# Sheet1.net
KiCad netlist of a schematic drawn in Altium Designer
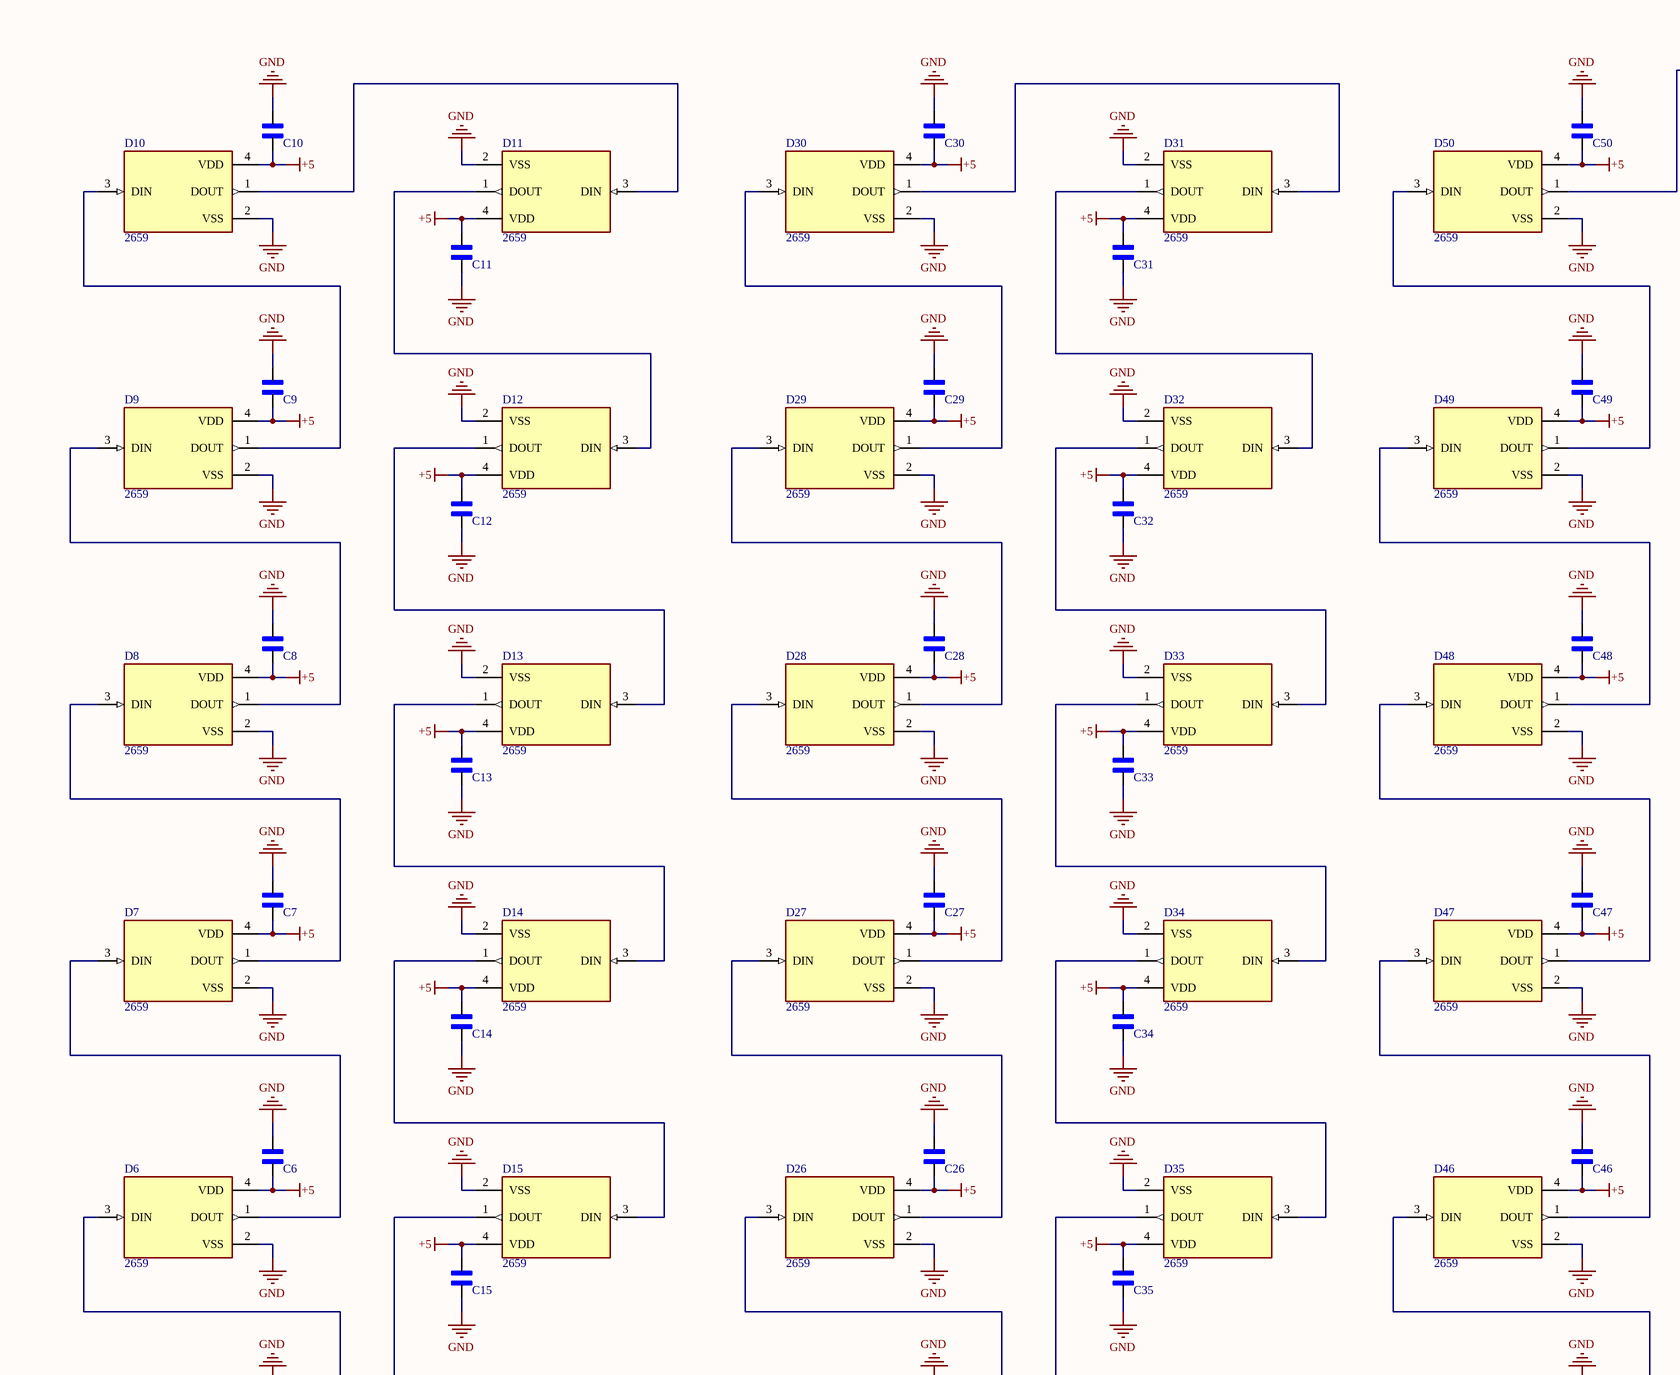
[diagram p0: Sheet1.SchDoc, top left]
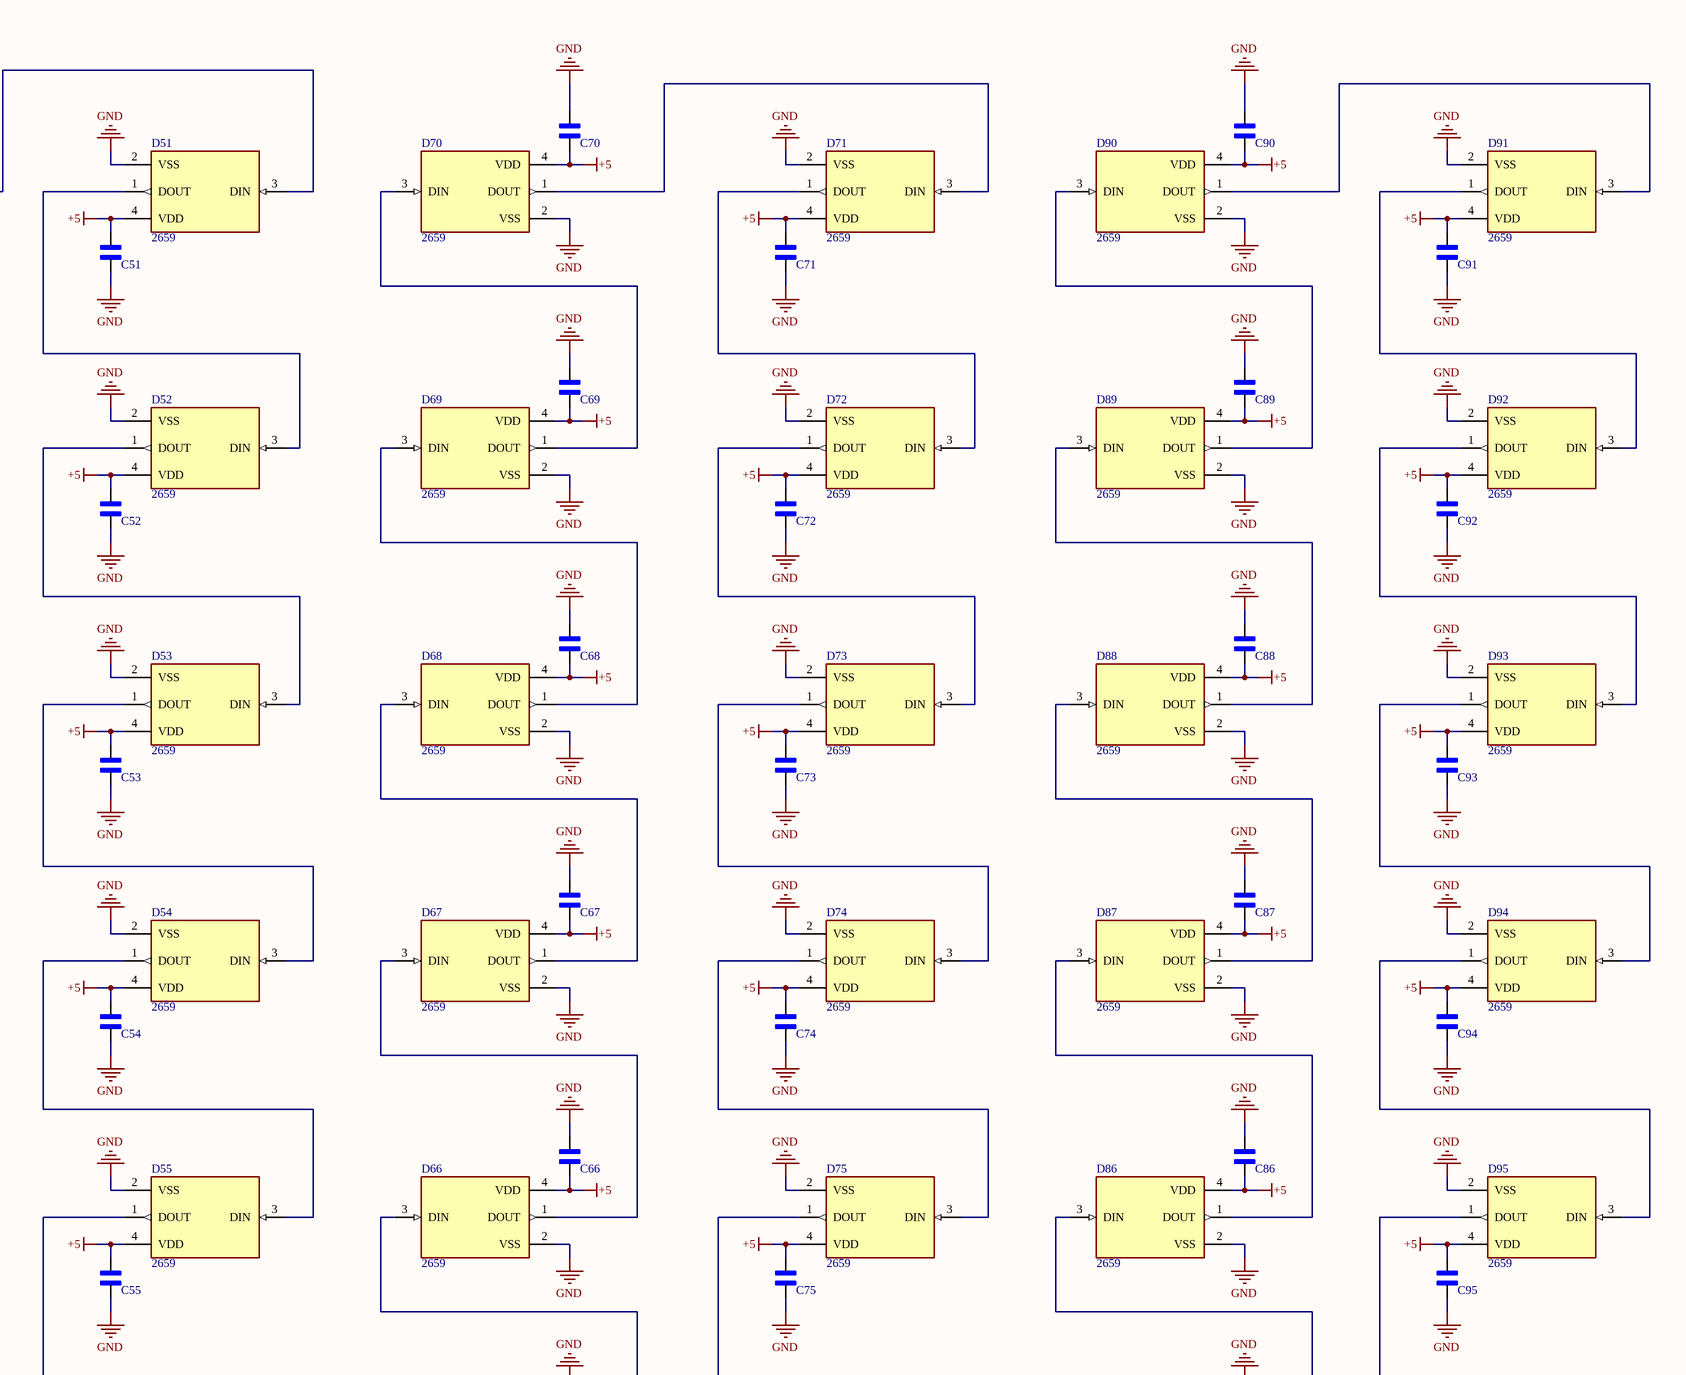
[diagram p1: Sheet1.SchDoc, top right]
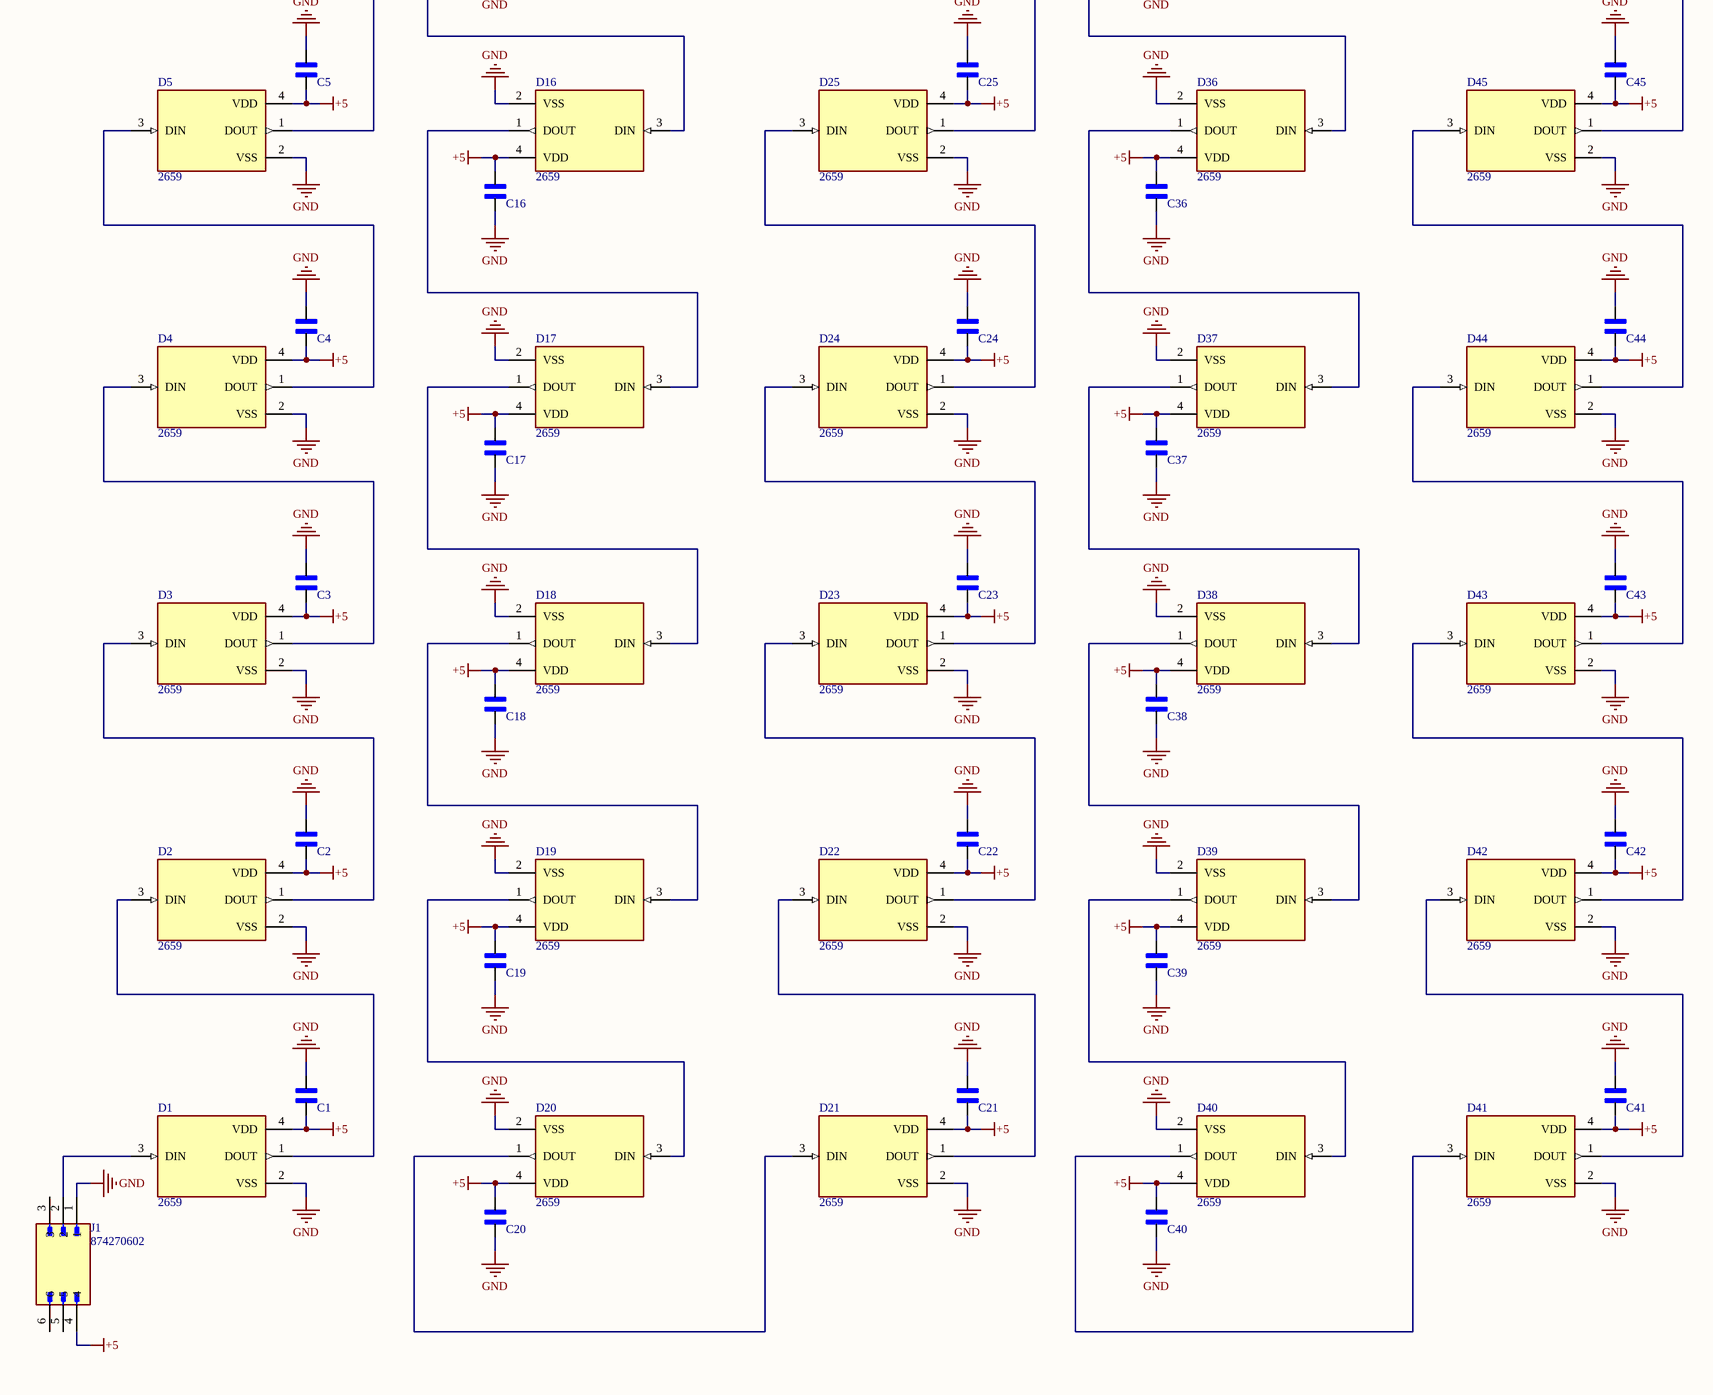
[diagram p2: Sheet1.SchDoc, bottom left]
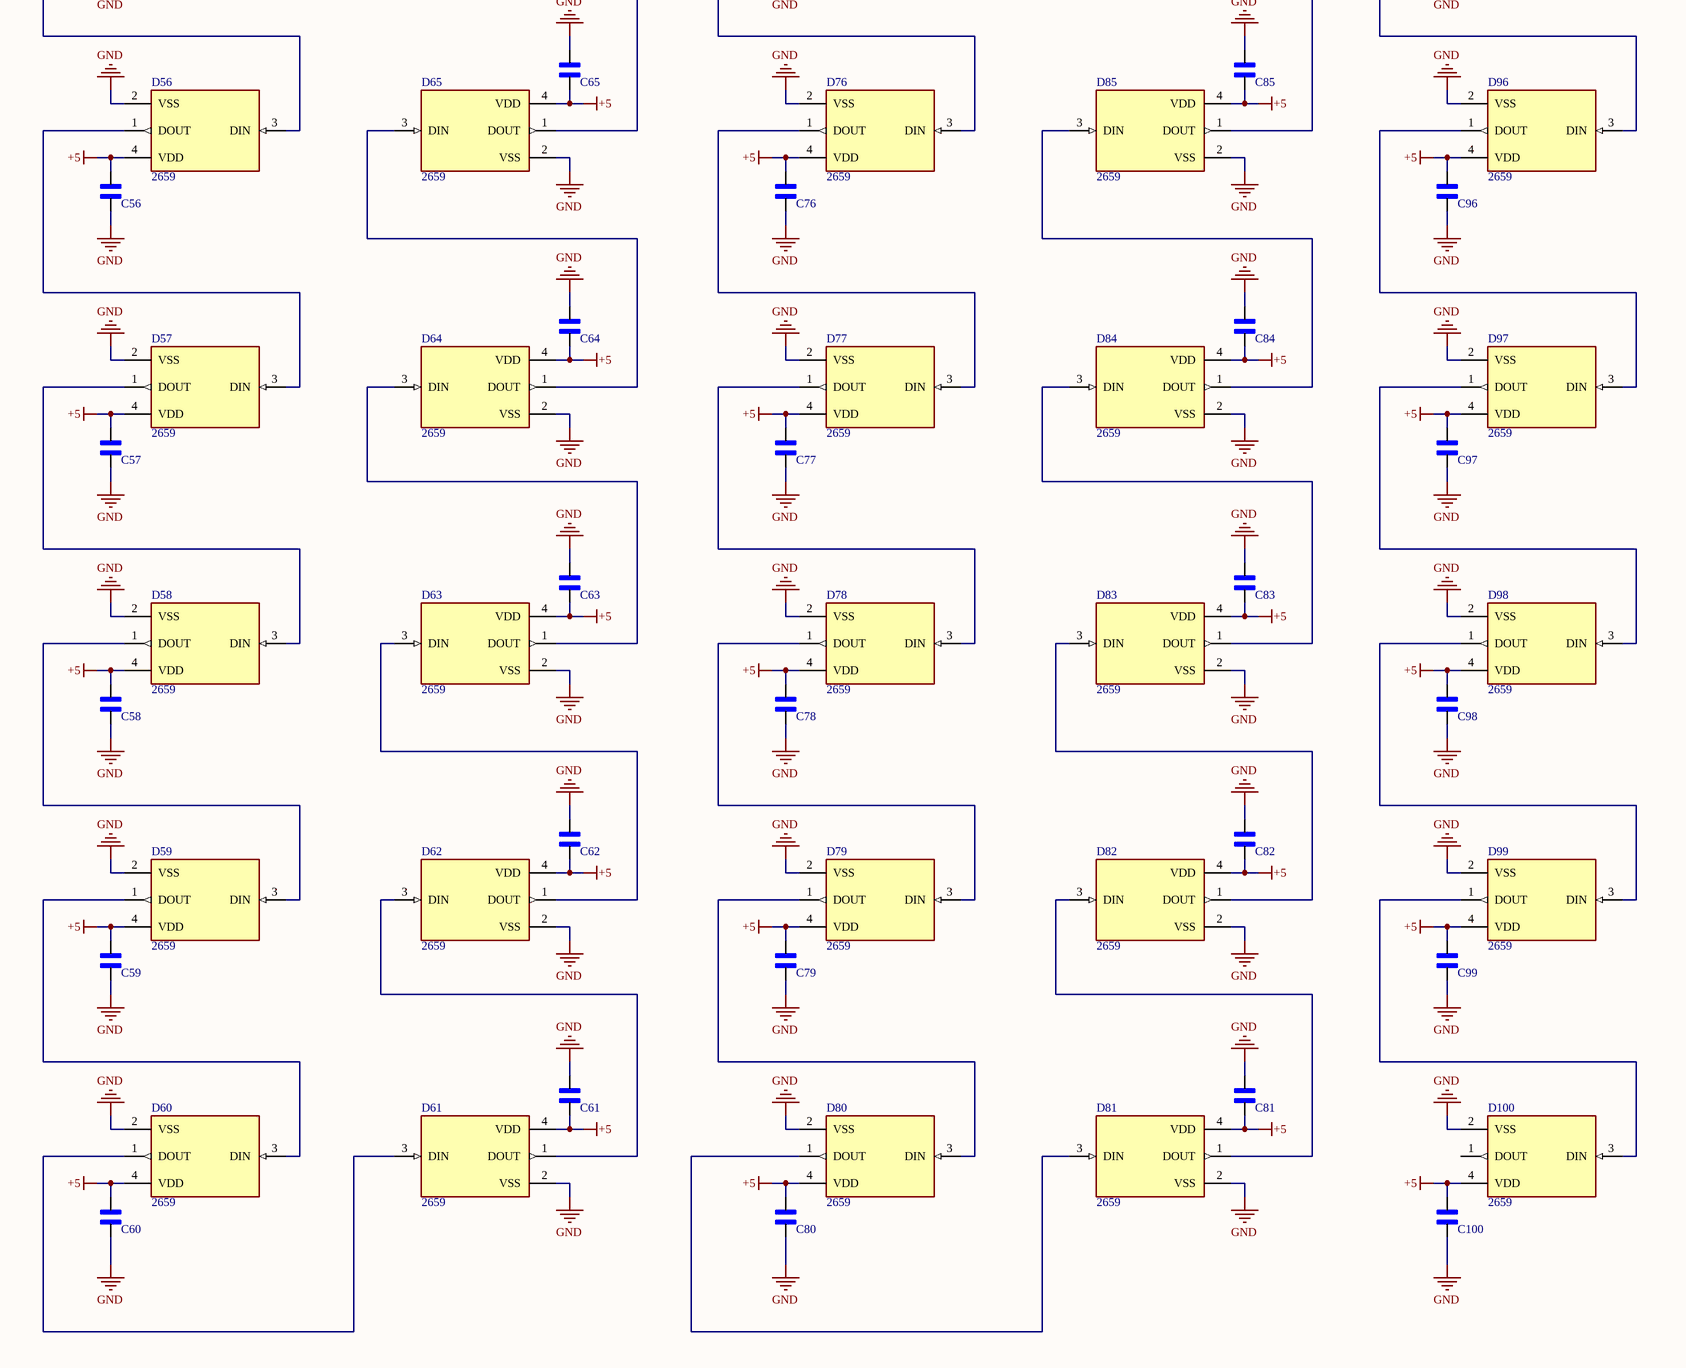
[diagram p3: Sheet1.SchDoc, bottom right]

(export (version "E")
  (design (tool "Eeschema 10.0.6"))
  (components
    (comp (ref "C1")
      (value "CL10B104KB8NNNC")
      (footprint "CL10B104KB8NNNC:CAPC1608X90N")
      (fields (field (name "MF") "{'manufacturer': u'Samsung Electro-Mechanics'}"))
      (libsource (lib "*") (part "CL10B104KB8NNNC"))
    )
    (comp (ref "C2")
      (value "CL10B104KB8NNNC")
      (footprint "CL10B104KB8NNNC:CAPC1608X90N")
      (fields (field (name "MF") "{'manufacturer': u'Samsung Electro-Mechanics'}"))
      (libsource (lib "*") (part "CL10B104KB8NNNC"))
    )
    (comp (ref "C3")
      (value "CL10B104KB8NNNC")
      (footprint "CL10B104KB8NNNC:CAPC1608X90N")
      (fields (field (name "MF") "{'manufacturer': u'Samsung Electro-Mechanics'}"))
      (libsource (lib "*") (part "CL10B104KB8NNNC"))
    )
    (comp (ref "C4")
      (value "CL10B104KB8NNNC")
      (footprint "CL10B104KB8NNNC:CAPC1608X90N")
      (fields (field (name "MF") "{'manufacturer': u'Samsung Electro-Mechanics'}"))
      (libsource (lib "*") (part "CL10B104KB8NNNC"))
    )
    (comp (ref "C5")
      (value "CL10B104KB8NNNC")
      (footprint "CL10B104KB8NNNC:CAPC1608X90N")
      (fields (field (name "MF") "{'manufacturer': u'Samsung Electro-Mechanics'}"))
      (libsource (lib "*") (part "CL10B104KB8NNNC"))
    )
    (comp (ref "C6")
      (value "CL10B104KB8NNNC")
      (footprint "CL10B104KB8NNNC:CAPC1608X90N")
      (fields (field (name "MF") "{'manufacturer': u'Samsung Electro-Mechanics'}"))
      (libsource (lib "*") (part "CL10B104KB8NNNC"))
    )
    (comp (ref "C7")
      (value "CL10B104KB8NNNC")
      (footprint "CL10B104KB8NNNC:CAPC1608X90N")
      (fields (field (name "MF") "{'manufacturer': u'Samsung Electro-Mechanics'}"))
      (libsource (lib "*") (part "CL10B104KB8NNNC"))
    )
    (comp (ref "C8")
      (value "CL10B104KB8NNNC")
      (footprint "CL10B104KB8NNNC:CAPC1608X90N")
      (fields (field (name "MF") "{'manufacturer': u'Samsung Electro-Mechanics'}"))
      (libsource (lib "*") (part "CL10B104KB8NNNC"))
    )
    (comp (ref "C9")
      (value "CL10B104KB8NNNC")
      (footprint "CL10B104KB8NNNC:CAPC1608X90N")
      (fields (field (name "MF") "{'manufacturer': u'Samsung Electro-Mechanics'}"))
      (libsource (lib "*") (part "CL10B104KB8NNNC"))
    )
    (comp (ref "C10")
      (value "CL10B104KB8NNNC")
      (footprint "CL10B104KB8NNNC:CAPC1608X90N")
      (fields (field (name "MF") "{'manufacturer': u'Samsung Electro-Mechanics'}"))
      (libsource (lib "*") (part "CL10B104KB8NNNC"))
    )
    (comp (ref "C11")
      (value "CL10B104KB8NNNC")
      (footprint "CL10B104KB8NNNC:CAPC1608X90N")
      (fields (field (name "MF") "{'manufacturer': u'Samsung Electro-Mechanics'}"))
      (libsource (lib "") (part "CL10B104KB8NNNC_1"))
    )
    (comp (ref "C12")
      (value "CL10B104KB8NNNC")
      (footprint "CL10B104KB8NNNC:CAPC1608X90N")
      (fields (field (name "MF") "{'manufacturer': u'Samsung Electro-Mechanics'}"))
      (libsource (lib "") (part "CL10B104KB8NNNC_1"))
    )
    (comp (ref "C13")
      (value "CL10B104KB8NNNC")
      (footprint "CL10B104KB8NNNC:CAPC1608X90N")
      (fields (field (name "MF") "{'manufacturer': u'Samsung Electro-Mechanics'}"))
      (libsource (lib "") (part "CL10B104KB8NNNC_1"))
    )
    (comp (ref "C14")
      (value "CL10B104KB8NNNC")
      (footprint "CL10B104KB8NNNC:CAPC1608X90N")
      (fields (field (name "MF") "{'manufacturer': u'Samsung Electro-Mechanics'}"))
      (libsource (lib "") (part "CL10B104KB8NNNC_1"))
    )
    (comp (ref "C15")
      (value "CL10B104KB8NNNC")
      (footprint "CL10B104KB8NNNC:CAPC1608X90N")
      (fields (field (name "MF") "{'manufacturer': u'Samsung Electro-Mechanics'}"))
      (libsource (lib "") (part "CL10B104KB8NNNC_1"))
    )
    (comp (ref "C16")
      (value "CL10B104KB8NNNC")
      (footprint "CL10B104KB8NNNC:CAPC1608X90N")
      (fields (field (name "MF") "{'manufacturer': u'Samsung Electro-Mechanics'}"))
      (libsource (lib "") (part "CL10B104KB8NNNC_1"))
    )
    (comp (ref "C17")
      (value "CL10B104KB8NNNC")
      (footprint "CL10B104KB8NNNC:CAPC1608X90N")
      (fields (field (name "MF") "{'manufacturer': u'Samsung Electro-Mechanics'}"))
      (libsource (lib "") (part "CL10B104KB8NNNC_1"))
    )
    (comp (ref "C18")
      (value "CL10B104KB8NNNC")
      (footprint "CL10B104KB8NNNC:CAPC1608X90N")
      (fields (field (name "MF") "{'manufacturer': u'Samsung Electro-Mechanics'}"))
      (libsource (lib "") (part "CL10B104KB8NNNC_1"))
    )
    (comp (ref "C19")
      (value "CL10B104KB8NNNC")
      (footprint "CL10B104KB8NNNC:CAPC1608X90N")
      (fields (field (name "MF") "{'manufacturer': u'Samsung Electro-Mechanics'}"))
      (libsource (lib "") (part "CL10B104KB8NNNC_1"))
    )
    (comp (ref "C20")
      (value "CL10B104KB8NNNC")
      (footprint "CL10B104KB8NNNC:CAPC1608X90N")
      (fields (field (name "MF") "{'manufacturer': u'Samsung Electro-Mechanics'}"))
      (libsource (lib "") (part "CL10B104KB8NNNC_1"))
    )
    (comp (ref "C21")
      (value "CL10B104KB8NNNC")
      (footprint "CL10B104KB8NNNC:CAPC1608X90N")
      (fields (field (name "MF") "{'manufacturer': u'Samsung Electro-Mechanics'}"))
      (libsource (lib "*") (part "CL10B104KB8NNNC"))
    )
    (comp (ref "C22")
      (value "CL10B104KB8NNNC")
      (footprint "CL10B104KB8NNNC:CAPC1608X90N")
      (fields (field (name "MF") "{'manufacturer': u'Samsung Electro-Mechanics'}"))
      (libsource (lib "*") (part "CL10B104KB8NNNC"))
    )
    (comp (ref "C23")
      (value "CL10B104KB8NNNC")
      (footprint "CL10B104KB8NNNC:CAPC1608X90N")
      (fields (field (name "MF") "{'manufacturer': u'Samsung Electro-Mechanics'}"))
      (libsource (lib "*") (part "CL10B104KB8NNNC"))
    )
    (comp (ref "C24")
      (value "CL10B104KB8NNNC")
      (footprint "CL10B104KB8NNNC:CAPC1608X90N")
      (fields (field (name "MF") "{'manufacturer': u'Samsung Electro-Mechanics'}"))
      (libsource (lib "*") (part "CL10B104KB8NNNC"))
    )
    (comp (ref "C25")
      (value "CL10B104KB8NNNC")
      (footprint "CL10B104KB8NNNC:CAPC1608X90N")
      (fields (field (name "MF") "{'manufacturer': u'Samsung Electro-Mechanics'}"))
      (libsource (lib "*") (part "CL10B104KB8NNNC"))
    )
    (comp (ref "C26")
      (value "CL10B104KB8NNNC")
      (footprint "CL10B104KB8NNNC:CAPC1608X90N")
      (fields (field (name "MF") "{'manufacturer': u'Samsung Electro-Mechanics'}"))
      (libsource (lib "*") (part "CL10B104KB8NNNC"))
    )
    (comp (ref "C27")
      (value "CL10B104KB8NNNC")
      (footprint "CL10B104KB8NNNC:CAPC1608X90N")
      (fields (field (name "MF") "{'manufacturer': u'Samsung Electro-Mechanics'}"))
      (libsource (lib "*") (part "CL10B104KB8NNNC"))
    )
    (comp (ref "C28")
      (value "CL10B104KB8NNNC")
      (footprint "CL10B104KB8NNNC:CAPC1608X90N")
      (fields (field (name "MF") "{'manufacturer': u'Samsung Electro-Mechanics'}"))
      (libsource (lib "*") (part "CL10B104KB8NNNC"))
    )
    (comp (ref "C29")
      (value "CL10B104KB8NNNC")
      (footprint "CL10B104KB8NNNC:CAPC1608X90N")
      (fields (field (name "MF") "{'manufacturer': u'Samsung Electro-Mechanics'}"))
      (libsource (lib "*") (part "CL10B104KB8NNNC"))
    )
    (comp (ref "C30")
      (value "CL10B104KB8NNNC")
      (footprint "CL10B104KB8NNNC:CAPC1608X90N")
      (fields (field (name "MF") "{'manufacturer': u'Samsung Electro-Mechanics'}"))
      (libsource (lib "*") (part "CL10B104KB8NNNC"))
    )
    (comp (ref "C31")
      (value "CL10B104KB8NNNC")
      (footprint "CL10B104KB8NNNC:CAPC1608X90N")
      (fields (field (name "MF") "{'manufacturer': u'Samsung Electro-Mechanics'}"))
      (libsource (lib "") (part "CL10B104KB8NNNC_1"))
    )
    (comp (ref "C32")
      (value "CL10B104KB8NNNC")
      (footprint "CL10B104KB8NNNC:CAPC1608X90N")
      (fields (field (name "MF") "{'manufacturer': u'Samsung Electro-Mechanics'}"))
      (libsource (lib "") (part "CL10B104KB8NNNC_1"))
    )
    (comp (ref "C33")
      (value "CL10B104KB8NNNC")
      (footprint "CL10B104KB8NNNC:CAPC1608X90N")
      (fields (field (name "MF") "{'manufacturer': u'Samsung Electro-Mechanics'}"))
      (libsource (lib "") (part "CL10B104KB8NNNC_1"))
    )
    (comp (ref "C34")
      (value "CL10B104KB8NNNC")
      (footprint "CL10B104KB8NNNC:CAPC1608X90N")
      (fields (field (name "MF") "{'manufacturer': u'Samsung Electro-Mechanics'}"))
      (libsource (lib "") (part "CL10B104KB8NNNC_1"))
    )
    (comp (ref "C35")
      (value "CL10B104KB8NNNC")
      (footprint "CL10B104KB8NNNC:CAPC1608X90N")
      (fields (field (name "MF") "{'manufacturer': u'Samsung Electro-Mechanics'}"))
      (libsource (lib "") (part "CL10B104KB8NNNC_1"))
    )
    (comp (ref "C36")
      (value "CL10B104KB8NNNC")
      (footprint "CL10B104KB8NNNC:CAPC1608X90N")
      (fields (field (name "MF") "{'manufacturer': u'Samsung Electro-Mechanics'}"))
      (libsource (lib "") (part "CL10B104KB8NNNC_1"))
    )
    (comp (ref "C37")
      (value "CL10B104KB8NNNC")
      (footprint "CL10B104KB8NNNC:CAPC1608X90N")
      (fields (field (name "MF") "{'manufacturer': u'Samsung Electro-Mechanics'}"))
      (libsource (lib "") (part "CL10B104KB8NNNC_1"))
    )
    (comp (ref "C38")
      (value "CL10B104KB8NNNC")
      (footprint "CL10B104KB8NNNC:CAPC1608X90N")
      (fields (field (name "MF") "{'manufacturer': u'Samsung Electro-Mechanics'}"))
      (libsource (lib "") (part "CL10B104KB8NNNC_1"))
    )
    (comp (ref "C39")
      (value "CL10B104KB8NNNC")
      (footprint "CL10B104KB8NNNC:CAPC1608X90N")
      (fields (field (name "MF") "{'manufacturer': u'Samsung Electro-Mechanics'}"))
      (libsource (lib "") (part "CL10B104KB8NNNC_1"))
    )
    (comp (ref "C40")
      (value "CL10B104KB8NNNC")
      (footprint "CL10B104KB8NNNC:CAPC1608X90N")
      (fields (field (name "MF") "{'manufacturer': u'Samsung Electro-Mechanics'}"))
      (libsource (lib "") (part "CL10B104KB8NNNC_1"))
    )
    (comp (ref "C41")
      (value "CL10B104KB8NNNC")
      (footprint "CL10B104KB8NNNC:CAPC1608X90N")
      (fields (field (name "MF") "{'manufacturer': u'Samsung Electro-Mechanics'}"))
      (libsource (lib "*") (part "CL10B104KB8NNNC"))
    )
    (comp (ref "C42")
      (value "CL10B104KB8NNNC")
      (footprint "CL10B104KB8NNNC:CAPC1608X90N")
      (fields (field (name "MF") "{'manufacturer': u'Samsung Electro-Mechanics'}"))
      (libsource (lib "*") (part "CL10B104KB8NNNC"))
    )
    (comp (ref "C43")
      (value "CL10B104KB8NNNC")
      (footprint "CL10B104KB8NNNC:CAPC1608X90N")
      (fields (field (name "MF") "{'manufacturer': u'Samsung Electro-Mechanics'}"))
      (libsource (lib "*") (part "CL10B104KB8NNNC"))
    )
    (comp (ref "C44")
      (value "CL10B104KB8NNNC")
      (footprint "CL10B104KB8NNNC:CAPC1608X90N")
      (fields (field (name "MF") "{'manufacturer': u'Samsung Electro-Mechanics'}"))
      (libsource (lib "*") (part "CL10B104KB8NNNC"))
    )
    (comp (ref "C45")
      (value "CL10B104KB8NNNC")
      (footprint "CL10B104KB8NNNC:CAPC1608X90N")
      (fields (field (name "MF") "{'manufacturer': u'Samsung Electro-Mechanics'}"))
      (libsource (lib "*") (part "CL10B104KB8NNNC"))
    )
    (comp (ref "C46")
      (value "CL10B104KB8NNNC")
      (footprint "CL10B104KB8NNNC:CAPC1608X90N")
      (fields (field (name "MF") "{'manufacturer': u'Samsung Electro-Mechanics'}"))
      (libsource (lib "*") (part "CL10B104KB8NNNC"))
    )
    (comp (ref "C47")
      (value "CL10B104KB8NNNC")
      (footprint "CL10B104KB8NNNC:CAPC1608X90N")
      (fields (field (name "MF") "{'manufacturer': u'Samsung Electro-Mechanics'}"))
      (libsource (lib "*") (part "CL10B104KB8NNNC"))
    )
    (comp (ref "C48")
      (value "CL10B104KB8NNNC")
      (footprint "CL10B104KB8NNNC:CAPC1608X90N")
      (fields (field (name "MF") "{'manufacturer': u'Samsung Electro-Mechanics'}"))
      (libsource (lib "*") (part "CL10B104KB8NNNC"))
    )
    (comp (ref "C49")
      (value "CL10B104KB8NNNC")
      (footprint "CL10B104KB8NNNC:CAPC1608X90N")
      (fields (field (name "MF") "{'manufacturer': u'Samsung Electro-Mechanics'}"))
      (libsource (lib "*") (part "CL10B104KB8NNNC"))
    )
    (comp (ref "C50")
      (value "CL10B104KB8NNNC")
      (footprint "CL10B104KB8NNNC:CAPC1608X90N")
      (fields (field (name "MF") "{'manufacturer': u'Samsung Electro-Mechanics'}"))
      (libsource (lib "*") (part "CL10B104KB8NNNC"))
    )
    (comp (ref "C51")
      (value "CL10B104KB8NNNC")
      (footprint "CL10B104KB8NNNC:CAPC1608X90N")
      (fields (field (name "MF") "{'manufacturer': u'Samsung Electro-Mechanics'}"))
      (libsource (lib "") (part "CL10B104KB8NNNC_1"))
    )
    (comp (ref "C52")
      (value "CL10B104KB8NNNC")
      (footprint "CL10B104KB8NNNC:CAPC1608X90N")
      (fields (field (name "MF") "{'manufacturer': u'Samsung Electro-Mechanics'}"))
      (libsource (lib "") (part "CL10B104KB8NNNC_1"))
    )
    (comp (ref "C53")
      (value "CL10B104KB8NNNC")
      (footprint "CL10B104KB8NNNC:CAPC1608X90N")
      (fields (field (name "MF") "{'manufacturer': u'Samsung Electro-Mechanics'}"))
      (libsource (lib "") (part "CL10B104KB8NNNC_1"))
    )
    (comp (ref "C54")
      (value "CL10B104KB8NNNC")
      (footprint "CL10B104KB8NNNC:CAPC1608X90N")
      (fields (field (name "MF") "{'manufacturer': u'Samsung Electro-Mechanics'}"))
      (libsource (lib "") (part "CL10B104KB8NNNC_1"))
    )
    (comp (ref "C55")
      (value "CL10B104KB8NNNC")
      (footprint "CL10B104KB8NNNC:CAPC1608X90N")
      (fields (field (name "MF") "{'manufacturer': u'Samsung Electro-Mechanics'}"))
      (libsource (lib "") (part "CL10B104KB8NNNC_1"))
    )
    (comp (ref "C56")
      (value "CL10B104KB8NNNC")
      (footprint "CL10B104KB8NNNC:CAPC1608X90N")
      (fields (field (name "MF") "{'manufacturer': u'Samsung Electro-Mechanics'}"))
      (libsource (lib "") (part "CL10B104KB8NNNC_1"))
    )
    (comp (ref "C57")
      (value "CL10B104KB8NNNC")
      (footprint "CL10B104KB8NNNC:CAPC1608X90N")
      (fields (field (name "MF") "{'manufacturer': u'Samsung Electro-Mechanics'}"))
      (libsource (lib "") (part "CL10B104KB8NNNC_1"))
    )
    (comp (ref "C58")
      (value "CL10B104KB8NNNC")
      (footprint "CL10B104KB8NNNC:CAPC1608X90N")
      (fields (field (name "MF") "{'manufacturer': u'Samsung Electro-Mechanics'}"))
      (libsource (lib "") (part "CL10B104KB8NNNC_1"))
    )
    (comp (ref "C59")
      (value "CL10B104KB8NNNC")
      (footprint "CL10B104KB8NNNC:CAPC1608X90N")
      (fields (field (name "MF") "{'manufacturer': u'Samsung Electro-Mechanics'}"))
      (libsource (lib "") (part "CL10B104KB8NNNC_1"))
    )
    (comp (ref "C60")
      (value "CL10B104KB8NNNC")
      (footprint "CL10B104KB8NNNC:CAPC1608X90N")
      (fields (field (name "MF") "{'manufacturer': u'Samsung Electro-Mechanics'}"))
      (libsource (lib "") (part "CL10B104KB8NNNC_1"))
    )
    (comp (ref "C61")
      (value "CL10B104KB8NNNC")
      (footprint "CL10B104KB8NNNC:CAPC1608X90N")
      (fields (field (name "MF") "{'manufacturer': u'Samsung Electro-Mechanics'}"))
      (libsource (lib "*") (part "CL10B104KB8NNNC"))
    )
    (comp (ref "C62")
      (value "CL10B104KB8NNNC")
      (footprint "CL10B104KB8NNNC:CAPC1608X90N")
      (fields (field (name "MF") "{'manufacturer': u'Samsung Electro-Mechanics'}"))
      (libsource (lib "*") (part "CL10B104KB8NNNC"))
    )
    (comp (ref "C63")
      (value "CL10B104KB8NNNC")
      (footprint "CL10B104KB8NNNC:CAPC1608X90N")
      (fields (field (name "MF") "{'manufacturer': u'Samsung Electro-Mechanics'}"))
      (libsource (lib "*") (part "CL10B104KB8NNNC"))
    )
    (comp (ref "C64")
      (value "CL10B104KB8NNNC")
      (footprint "CL10B104KB8NNNC:CAPC1608X90N")
      (fields (field (name "MF") "{'manufacturer': u'Samsung Electro-Mechanics'}"))
      (libsource (lib "*") (part "CL10B104KB8NNNC"))
    )
    (comp (ref "C65")
      (value "CL10B104KB8NNNC")
      (footprint "CL10B104KB8NNNC:CAPC1608X90N")
      (fields (field (name "MF") "{'manufacturer': u'Samsung Electro-Mechanics'}"))
      (libsource (lib "*") (part "CL10B104KB8NNNC"))
    )
    (comp (ref "C66")
      (value "CL10B104KB8NNNC")
      (footprint "CL10B104KB8NNNC:CAPC1608X90N")
      (fields (field (name "MF") "{'manufacturer': u'Samsung Electro-Mechanics'}"))
      (libsource (lib "*") (part "CL10B104KB8NNNC"))
    )
    (comp (ref "C67")
      (value "CL10B104KB8NNNC")
      (footprint "CL10B104KB8NNNC:CAPC1608X90N")
      (fields (field (name "MF") "{'manufacturer': u'Samsung Electro-Mechanics'}"))
      (libsource (lib "*") (part "CL10B104KB8NNNC"))
    )
    (comp (ref "C68")
      (value "CL10B104KB8NNNC")
      (footprint "CL10B104KB8NNNC:CAPC1608X90N")
      (fields (field (name "MF") "{'manufacturer': u'Samsung Electro-Mechanics'}"))
      (libsource (lib "*") (part "CL10B104KB8NNNC"))
    )
    (comp (ref "C69")
      (value "CL10B104KB8NNNC")
      (footprint "CL10B104KB8NNNC:CAPC1608X90N")
      (fields (field (name "MF") "{'manufacturer': u'Samsung Electro-Mechanics'}"))
      (libsource (lib "*") (part "CL10B104KB8NNNC"))
    )
    (comp (ref "C70")
      (value "CL10B104KB8NNNC")
      (footprint "CL10B104KB8NNNC:CAPC1608X90N")
      (fields (field (name "MF") "{'manufacturer': u'Samsung Electro-Mechanics'}"))
      (libsource (lib "*") (part "CL10B104KB8NNNC"))
    )
    (comp (ref "C71")
      (value "CL10B104KB8NNNC")
      (footprint "CL10B104KB8NNNC:CAPC1608X90N")
      (fields (field (name "MF") "{'manufacturer': u'Samsung Electro-Mechanics'}"))
      (libsource (lib "") (part "CL10B104KB8NNNC_1"))
    )
    (comp (ref "C72")
      (value "CL10B104KB8NNNC")
      (footprint "CL10B104KB8NNNC:CAPC1608X90N")
      (fields (field (name "MF") "{'manufacturer': u'Samsung Electro-Mechanics'}"))
      (libsource (lib "") (part "CL10B104KB8NNNC_1"))
    )
    (comp (ref "C73")
      (value "CL10B104KB8NNNC")
      (footprint "CL10B104KB8NNNC:CAPC1608X90N")
      (fields (field (name "MF") "{'manufacturer': u'Samsung Electro-Mechanics'}"))
      (libsource (lib "") (part "CL10B104KB8NNNC_1"))
    )
    (comp (ref "C74")
      (value "CL10B104KB8NNNC")
      (footprint "CL10B104KB8NNNC:CAPC1608X90N")
      (fields (field (name "MF") "{'manufacturer': u'Samsung Electro-Mechanics'}"))
      (libsource (lib "") (part "CL10B104KB8NNNC_1"))
    )
    (comp (ref "C75")
      (value "CL10B104KB8NNNC")
      (footprint "CL10B104KB8NNNC:CAPC1608X90N")
      (fields (field (name "MF") "{'manufacturer': u'Samsung Electro-Mechanics'}"))
      (libsource (lib "") (part "CL10B104KB8NNNC_1"))
    )
    (comp (ref "C76")
      (value "CL10B104KB8NNNC")
      (footprint "CL10B104KB8NNNC:CAPC1608X90N")
      (fields (field (name "MF") "{'manufacturer': u'Samsung Electro-Mechanics'}"))
      (libsource (lib "") (part "CL10B104KB8NNNC_1"))
    )
    (comp (ref "C77")
      (value "CL10B104KB8NNNC")
      (footprint "CL10B104KB8NNNC:CAPC1608X90N")
      (fields (field (name "MF") "{'manufacturer': u'Samsung Electro-Mechanics'}"))
      (libsource (lib "") (part "CL10B104KB8NNNC_1"))
    )
    (comp (ref "C78")
      (value "CL10B104KB8NNNC")
      (footprint "CL10B104KB8NNNC:CAPC1608X90N")
      (fields (field (name "MF") "{'manufacturer': u'Samsung Electro-Mechanics'}"))
      (libsource (lib "") (part "CL10B104KB8NNNC_1"))
    )
    (comp (ref "C79")
      (value "CL10B104KB8NNNC")
      (footprint "CL10B104KB8NNNC:CAPC1608X90N")
      (fields (field (name "MF") "{'manufacturer': u'Samsung Electro-Mechanics'}"))
      (libsource (lib "") (part "CL10B104KB8NNNC_1"))
    )
    (comp (ref "C80")
      (value "CL10B104KB8NNNC")
      (footprint "CL10B104KB8NNNC:CAPC1608X90N")
      (fields (field (name "MF") "{'manufacturer': u'Samsung Electro-Mechanics'}"))
      (libsource (lib "") (part "CL10B104KB8NNNC_1"))
    )
    (comp (ref "C81")
      (value "CL10B104KB8NNNC")
      (footprint "CL10B104KB8NNNC:CAPC1608X90N")
      (fields (field (name "MF") "{'manufacturer': u'Samsung Electro-Mechanics'}"))
      (libsource (lib "*") (part "CL10B104KB8NNNC"))
    )
    (comp (ref "C82")
      (value "CL10B104KB8NNNC")
      (footprint "CL10B104KB8NNNC:CAPC1608X90N")
      (fields (field (name "MF") "{'manufacturer': u'Samsung Electro-Mechanics'}"))
      (libsource (lib "*") (part "CL10B104KB8NNNC"))
    )
    (comp (ref "C83")
      (value "CL10B104KB8NNNC")
      (footprint "CL10B104KB8NNNC:CAPC1608X90N")
      (fields (field (name "MF") "{'manufacturer': u'Samsung Electro-Mechanics'}"))
      (libsource (lib "*") (part "CL10B104KB8NNNC"))
    )
    (comp (ref "C84")
      (value "CL10B104KB8NNNC")
      (footprint "CL10B104KB8NNNC:CAPC1608X90N")
      (fields (field (name "MF") "{'manufacturer': u'Samsung Electro-Mechanics'}"))
      (libsource (lib "*") (part "CL10B104KB8NNNC"))
    )
    (comp (ref "C85")
      (value "CL10B104KB8NNNC")
      (footprint "CL10B104KB8NNNC:CAPC1608X90N")
      (fields (field (name "MF") "{'manufacturer': u'Samsung Electro-Mechanics'}"))
      (libsource (lib "*") (part "CL10B104KB8NNNC"))
    )
    (comp (ref "C86")
      (value "CL10B104KB8NNNC")
      (footprint "CL10B104KB8NNNC:CAPC1608X90N")
      (fields (field (name "MF") "{'manufacturer': u'Samsung Electro-Mechanics'}"))
      (libsource (lib "*") (part "CL10B104KB8NNNC"))
    )
    (comp (ref "C87")
      (value "CL10B104KB8NNNC")
      (footprint "CL10B104KB8NNNC:CAPC1608X90N")
      (fields (field (name "MF") "{'manufacturer': u'Samsung Electro-Mechanics'}"))
      (libsource (lib "*") (part "CL10B104KB8NNNC"))
    )
    (comp (ref "C88")
      (value "CL10B104KB8NNNC")
      (footprint "CL10B104KB8NNNC:CAPC1608X90N")
      (fields (field (name "MF") "{'manufacturer': u'Samsung Electro-Mechanics'}"))
      (libsource (lib "*") (part "CL10B104KB8NNNC"))
    )
    (comp (ref "C89")
      (value "CL10B104KB8NNNC")
      (footprint "CL10B104KB8NNNC:CAPC1608X90N")
      (fields (field (name "MF") "{'manufacturer': u'Samsung Electro-Mechanics'}"))
      (libsource (lib "*") (part "CL10B104KB8NNNC"))
    )
    (comp (ref "C90")
      (value "CL10B104KB8NNNC")
      (footprint "CL10B104KB8NNNC:CAPC1608X90N")
      (fields (field (name "MF") "{'manufacturer': u'Samsung Electro-Mechanics'}"))
      (libsource (lib "*") (part "CL10B104KB8NNNC"))
    )
    (comp (ref "C91")
      (value "CL10B104KB8NNNC")
      (footprint "CL10B104KB8NNNC:CAPC1608X90N")
      (fields (field (name "MF") "{'manufacturer': u'Samsung Electro-Mechanics'}"))
      (libsource (lib "") (part "CL10B104KB8NNNC_1"))
    )
    (comp (ref "C92")
      (value "CL10B104KB8NNNC")
      (footprint "CL10B104KB8NNNC:CAPC1608X90N")
      (fields (field (name "MF") "{'manufacturer': u'Samsung Electro-Mechanics'}"))
      (libsource (lib "") (part "CL10B104KB8NNNC_1"))
    )
    (comp (ref "C93")
      (value "CL10B104KB8NNNC")
      (footprint "CL10B104KB8NNNC:CAPC1608X90N")
      (fields (field (name "MF") "{'manufacturer': u'Samsung Electro-Mechanics'}"))
      (libsource (lib "") (part "CL10B104KB8NNNC_1"))
    )
    (comp (ref "C94")
      (value "CL10B104KB8NNNC")
      (footprint "CL10B104KB8NNNC:CAPC1608X90N")
      (fields (field (name "MF") "{'manufacturer': u'Samsung Electro-Mechanics'}"))
      (libsource (lib "") (part "CL10B104KB8NNNC_1"))
    )
    (comp (ref "C95")
      (value "CL10B104KB8NNNC")
      (footprint "CL10B104KB8NNNC:CAPC1608X90N")
      (fields (field (name "MF") "{'manufacturer': u'Samsung Electro-Mechanics'}"))
      (libsource (lib "") (part "CL10B104KB8NNNC_1"))
    )
    (comp (ref "C96")
      (value "CL10B104KB8NNNC")
      (footprint "CL10B104KB8NNNC:CAPC1608X90N")
      (fields (field (name "MF") "{'manufacturer': u'Samsung Electro-Mechanics'}"))
      (libsource (lib "") (part "CL10B104KB8NNNC_1"))
    )
    (comp (ref "C97")
      (value "CL10B104KB8NNNC")
      (footprint "CL10B104KB8NNNC:CAPC1608X90N")
      (fields (field (name "MF") "{'manufacturer': u'Samsung Electro-Mechanics'}"))
      (libsource (lib "") (part "CL10B104KB8NNNC_1"))
    )
    (comp (ref "C98")
      (value "CL10B104KB8NNNC")
      (footprint "CL10B104KB8NNNC:CAPC1608X90N")
      (fields (field (name "MF") "{'manufacturer': u'Samsung Electro-Mechanics'}"))
      (libsource (lib "") (part "CL10B104KB8NNNC_1"))
    )
    (comp (ref "C99")
      (value "CL10B104KB8NNNC")
      (footprint "CL10B104KB8NNNC:CAPC1608X90N")
      (fields (field (name "MF") "{'manufacturer': u'Samsung Electro-Mechanics'}"))
      (libsource (lib "") (part "CL10B104KB8NNNC_1"))
    )
    (comp (ref "C100")
      (value "CL10B104KB8NNNC")
      (footprint "CL10B104KB8NNNC:CAPC1608X90N")
      (fields (field (name "MF") "{'manufacturer': u'Samsung Electro-Mechanics'}"))
      (libsource (lib "") (part "CL10B104KB8NNNC_1"))
    )
    (comp (ref "D1")
      (value "2659")
      (footprint "2659")
      (description "20 AWG Hook-Up Wire 26/34 White 300V 40.00' _12.19m_")
      (fields (field (name "MF") "Adafruit Industries") (field (name "DIGI-KEY_PART_NUMBER") "2183-2659-ND"))
      (libsource (lib "") (part "2659_1"))
    )
    (comp (ref "D2")
      (value "2659")
      (footprint "2659")
      (description "20 AWG Hook-Up Wire 26/34 White 300V 40.00' _12.19m_")
      (fields (field (name "MF") "Adafruit Industries") (field (name "DIGI-KEY_PART_NUMBER") "2183-2659-ND"))
      (libsource (lib "") (part "2659_1"))
    )
    (comp (ref "D3")
      (value "2659")
      (footprint "2659")
      (description "20 AWG Hook-Up Wire 26/34 White 300V 40.00' _12.19m_")
      (fields (field (name "MF") "Adafruit Industries") (field (name "DIGI-KEY_PART_NUMBER") "2183-2659-ND"))
      (libsource (lib "") (part "2659_1"))
    )
    (comp (ref "D4")
      (value "2659")
      (footprint "2659")
      (description "20 AWG Hook-Up Wire 26/34 White 300V 40.00' _12.19m_")
      (fields (field (name "MF") "Adafruit Industries") (field (name "DIGI-KEY_PART_NUMBER") "2183-2659-ND"))
      (libsource (lib "") (part "2659_1"))
    )
    (comp (ref "D5")
      (value "2659")
      (footprint "2659")
      (description "20 AWG Hook-Up Wire 26/34 White 300V 40.00' _12.19m_")
      (fields (field (name "MF") "Adafruit Industries") (field (name "DIGI-KEY_PART_NUMBER") "2183-2659-ND"))
      (libsource (lib "") (part "2659_1"))
    )
    (comp (ref "D6")
      (value "2659")
      (footprint "2659")
      (description "20 AWG Hook-Up Wire 26/34 White 300V 40.00' _12.19m_")
      (fields (field (name "MF") "Adafruit Industries") (field (name "DIGI-KEY_PART_NUMBER") "2183-2659-ND"))
      (libsource (lib "") (part "2659_1"))
    )
    (comp (ref "D7")
      (value "2659")
      (footprint "2659")
      (description "20 AWG Hook-Up Wire 26/34 White 300V 40.00' _12.19m_")
      (fields (field (name "MF") "Adafruit Industries") (field (name "DIGI-KEY_PART_NUMBER") "2183-2659-ND"))
      (libsource (lib "") (part "2659_1"))
    )
    (comp (ref "D8")
      (value "2659")
      (footprint "2659")
      (description "20 AWG Hook-Up Wire 26/34 White 300V 40.00' _12.19m_")
      (fields (field (name "MF") "Adafruit Industries") (field (name "DIGI-KEY_PART_NUMBER") "2183-2659-ND"))
      (libsource (lib "") (part "2659_1"))
    )
    (comp (ref "D9")
      (value "2659")
      (footprint "2659")
      (description "20 AWG Hook-Up Wire 26/34 White 300V 40.00' _12.19m_")
      (fields (field (name "MF") "Adafruit Industries") (field (name "DIGI-KEY_PART_NUMBER") "2183-2659-ND"))
      (libsource (lib "") (part "2659_1"))
    )
    (comp (ref "D10")
      (value "2659")
      (footprint "2659")
      (description "20 AWG Hook-Up Wire 26/34 White 300V 40.00' _12.19m_")
      (fields (field (name "MF") "Adafruit Industries") (field (name "DIGI-KEY_PART_NUMBER") "2183-2659-ND"))
      (libsource (lib "") (part "2659_1"))
    )
    (comp (ref "D11")
      (value "2659")
      (footprint "2659")
      (description "20 AWG Hook-Up Wire 26/34 White 300V 40.00' _12.19m_")
      (fields (field (name "MF") "Adafruit Industries") (field (name "DIGI-KEY_PART_NUMBER") "2183-2659-ND"))
      (libsource (lib "Michal") (part "2659"))
    )
    (comp (ref "D12")
      (value "2659")
      (footprint "2659")
      (description "20 AWG Hook-Up Wire 26/34 White 300V 40.00' _12.19m_")
      (fields (field (name "MF") "Adafruit Industries") (field (name "DIGI-KEY_PART_NUMBER") "2183-2659-ND"))
      (libsource (lib "Michal") (part "2659"))
    )
    (comp (ref "D13")
      (value "2659")
      (footprint "2659")
      (description "20 AWG Hook-Up Wire 26/34 White 300V 40.00' _12.19m_")
      (fields (field (name "MF") "Adafruit Industries") (field (name "DIGI-KEY_PART_NUMBER") "2183-2659-ND"))
      (libsource (lib "Michal") (part "2659"))
    )
    (comp (ref "D14")
      (value "2659")
      (footprint "2659")
      (description "20 AWG Hook-Up Wire 26/34 White 300V 40.00' _12.19m_")
      (fields (field (name "MF") "Adafruit Industries") (field (name "DIGI-KEY_PART_NUMBER") "2183-2659-ND"))
      (libsource (lib "Michal") (part "2659"))
    )
    (comp (ref "D15")
      (value "2659")
      (footprint "2659")
      (description "20 AWG Hook-Up Wire 26/34 White 300V 40.00' _12.19m_")
      (fields (field (name "MF") "Adafruit Industries") (field (name "DIGI-KEY_PART_NUMBER") "2183-2659-ND"))
      (libsource (lib "Michal") (part "2659"))
    )
    (comp (ref "D16")
      (value "2659")
      (footprint "2659")
      (description "20 AWG Hook-Up Wire 26/34 White 300V 40.00' _12.19m_")
      (fields (field (name "MF") "Adafruit Industries") (field (name "DIGI-KEY_PART_NUMBER") "2183-2659-ND"))
      (libsource (lib "Michal") (part "2659"))
    )
    (comp (ref "D17")
      (value "2659")
      (footprint "2659")
      (description "20 AWG Hook-Up Wire 26/34 White 300V 40.00' _12.19m_")
      (fields (field (name "MF") "Adafruit Industries") (field (name "DIGI-KEY_PART_NUMBER") "2183-2659-ND"))
      (libsource (lib "Michal") (part "2659"))
    )
    (comp (ref "D18")
      (value "2659")
      (footprint "2659")
      (description "20 AWG Hook-Up Wire 26/34 White 300V 40.00' _12.19m_")
      (fields (field (name "MF") "Adafruit Industries") (field (name "DIGI-KEY_PART_NUMBER") "2183-2659-ND"))
      (libsource (lib "Michal") (part "2659"))
    )
    (comp (ref "D19")
      (value "2659")
      (footprint "2659")
      (description "20 AWG Hook-Up Wire 26/34 White 300V 40.00' _12.19m_")
      (fields (field (name "MF") "Adafruit Industries") (field (name "DIGI-KEY_PART_NUMBER") "2183-2659-ND"))
      (libsource (lib "Michal") (part "2659"))
    )
    (comp (ref "D20")
      (value "2659")
      (footprint "2659")
      (description "20 AWG Hook-Up Wire 26/34 White 300V 40.00' _12.19m_")
      (fields (field (name "MF") "Adafruit Industries") (field (name "DIGI-KEY_PART_NUMBER") "2183-2659-ND"))
      (libsource (lib "Michal") (part "2659"))
    )
    (comp (ref "D21")
      (value "2659")
      (footprint "2659")
      (description "20 AWG Hook-Up Wire 26/34 White 300V 40.00' _12.19m_")
      (fields (field (name "MF") "Adafruit Industries") (field (name "DIGI-KEY_PART_NUMBER") "2183-2659-ND"))
      (libsource (lib "") (part "2659_1"))
    )
    (comp (ref "D22")
      (value "2659")
      (footprint "2659")
      (description "20 AWG Hook-Up Wire 26/34 White 300V 40.00' _12.19m_")
      (fields (field (name "MF") "Adafruit Industries") (field (name "DIGI-KEY_PART_NUMBER") "2183-2659-ND"))
      (libsource (lib "") (part "2659_1"))
    )
    (comp (ref "D23")
      (value "2659")
      (footprint "2659")
      (description "20 AWG Hook-Up Wire 26/34 White 300V 40.00' _12.19m_")
      (fields (field (name "MF") "Adafruit Industries") (field (name "DIGI-KEY_PART_NUMBER") "2183-2659-ND"))
      (libsource (lib "") (part "2659_1"))
    )
    (comp (ref "D24")
      (value "2659")
      (footprint "2659")
      (description "20 AWG Hook-Up Wire 26/34 White 300V 40.00' _12.19m_")
      (fields (field (name "MF") "Adafruit Industries") (field (name "DIGI-KEY_PART_NUMBER") "2183-2659-ND"))
      (libsource (lib "") (part "2659_1"))
    )
    (comp (ref "D25")
      (value "2659")
      (footprint "2659")
      (description "20 AWG Hook-Up Wire 26/34 White 300V 40.00' _12.19m_")
      (fields (field (name "MF") "Adafruit Industries") (field (name "DIGI-KEY_PART_NUMBER") "2183-2659-ND"))
      (libsource (lib "") (part "2659_1"))
    )
    (comp (ref "D26")
      (value "2659")
      (footprint "2659")
      (description "20 AWG Hook-Up Wire 26/34 White 300V 40.00' _12.19m_")
      (fields (field (name "MF") "Adafruit Industries") (field (name "DIGI-KEY_PART_NUMBER") "2183-2659-ND"))
      (libsource (lib "") (part "2659_1"))
    )
    (comp (ref "D27")
      (value "2659")
      (footprint "2659")
      (description "20 AWG Hook-Up Wire 26/34 White 300V 40.00' _12.19m_")
      (fields (field (name "MF") "Adafruit Industries") (field (name "DIGI-KEY_PART_NUMBER") "2183-2659-ND"))
      (libsource (lib "") (part "2659_1"))
    )
    (comp (ref "D28")
      (value "2659")
      (footprint "2659")
      (description "20 AWG Hook-Up Wire 26/34 White 300V 40.00' _12.19m_")
      (fields (field (name "MF") "Adafruit Industries") (field (name "DIGI-KEY_PART_NUMBER") "2183-2659-ND"))
      (libsource (lib "") (part "2659_1"))
    )
    (comp (ref "D29")
      (value "2659")
      (footprint "2659")
      (description "20 AWG Hook-Up Wire 26/34 White 300V 40.00' _12.19m_")
      (fields (field (name "MF") "Adafruit Industries") (field (name "DIGI-KEY_PART_NUMBER") "2183-2659-ND"))
      (libsource (lib "") (part "2659_1"))
    )
    (comp (ref "D30")
      (value "2659")
      (footprint "2659")
      (description "20 AWG Hook-Up Wire 26/34 White 300V 40.00' _12.19m_")
      (fields (field (name "MF") "Adafruit Industries") (field (name "DIGI-KEY_PART_NUMBER") "2183-2659-ND"))
      (libsource (lib "") (part "2659_1"))
    )
    (comp (ref "D31")
      (value "2659")
      (footprint "2659")
      (description "20 AWG Hook-Up Wire 26/34 White 300V 40.00' _12.19m_")
      (fields (field (name "MF") "Adafruit Industries") (field (name "DIGI-KEY_PART_NUMBER") "2183-2659-ND"))
      (libsource (lib "Michal") (part "2659"))
    )
    (comp (ref "D32")
      (value "2659")
      (footprint "2659")
      (description "20 AWG Hook-Up Wire 26/34 White 300V 40.00' _12.19m_")
      (fields (field (name "MF") "Adafruit Industries") (field (name "DIGI-KEY_PART_NUMBER") "2183-2659-ND"))
      (libsource (lib "Michal") (part "2659"))
    )
    (comp (ref "D33")
      (value "2659")
      (footprint "2659")
      (description "20 AWG Hook-Up Wire 26/34 White 300V 40.00' _12.19m_")
      (fields (field (name "MF") "Adafruit Industries") (field (name "DIGI-KEY_PART_NUMBER") "2183-2659-ND"))
      (libsource (lib "Michal") (part "2659"))
    )
    (comp (ref "D34")
      (value "2659")
      (footprint "2659")
      (description "20 AWG Hook-Up Wire 26/34 White 300V 40.00' _12.19m_")
      (fields (field (name "MF") "Adafruit Industries") (field (name "DIGI-KEY_PART_NUMBER") "2183-2659-ND"))
      (libsource (lib "Michal") (part "2659"))
    )
    (comp (ref "D35")
      (value "2659")
      (footprint "2659")
      (description "20 AWG Hook-Up Wire 26/34 White 300V 40.00' _12.19m_")
      (fields (field (name "MF") "Adafruit Industries") (field (name "DIGI-KEY_PART_NUMBER") "2183-2659-ND"))
      (libsource (lib "Michal") (part "2659"))
    )
    (comp (ref "D36")
      (value "2659")
      (footprint "2659")
      (description "20 AWG Hook-Up Wire 26/34 White 300V 40.00' _12.19m_")
      (fields (field (name "MF") "Adafruit Industries") (field (name "DIGI-KEY_PART_NUMBER") "2183-2659-ND"))
      (libsource (lib "Michal") (part "2659"))
    )
    (comp (ref "D37")
      (value "2659")
      (footprint "2659")
      (description "20 AWG Hook-Up Wire 26/34 White 300V 40.00' _12.19m_")
      (fields (field (name "MF") "Adafruit Industries") (field (name "DIGI-KEY_PART_NUMBER") "2183-2659-ND"))
      (libsource (lib "Michal") (part "2659"))
    )
    (comp (ref "D38")
      (value "2659")
      (footprint "2659")
      (description "20 AWG Hook-Up Wire 26/34 White 300V 40.00' _12.19m_")
      (fields (field (name "MF") "Adafruit Industries") (field (name "DIGI-KEY_PART_NUMBER") "2183-2659-ND"))
      (libsource (lib "Michal") (part "2659"))
    )
    (comp (ref "D39")
      (value "2659")
      (footprint "2659")
      (description "20 AWG Hook-Up Wire 26/34 White 300V 40.00' _12.19m_")
      (fields (field (name "MF") "Adafruit Industries") (field (name "DIGI-KEY_PART_NUMBER") "2183-2659-ND"))
      (libsource (lib "Michal") (part "2659"))
    )
    (comp (ref "D40")
      (value "2659")
      (footprint "2659")
      (description "20 AWG Hook-Up Wire 26/34 White 300V 40.00' _12.19m_")
      (fields (field (name "MF") "Adafruit Industries") (field (name "DIGI-KEY_PART_NUMBER") "2183-2659-ND"))
      (libsource (lib "Michal") (part "2659"))
    )
    (comp (ref "D41")
      (value "2659")
      (footprint "2659")
      (description "20 AWG Hook-Up Wire 26/34 White 300V 40.00' _12.19m_")
      (fields (field (name "MF") "Adafruit Industries") (field (name "DIGI-KEY_PART_NUMBER") "2183-2659-ND"))
      (libsource (lib "") (part "2659_1"))
    )
    (comp (ref "D42")
      (value "2659")
      (footprint "2659")
      (description "20 AWG Hook-Up Wire 26/34 White 300V 40.00' _12.19m_")
      (fields (field (name "MF") "Adafruit Industries") (field (name "DIGI-KEY_PART_NUMBER") "2183-2659-ND"))
      (libsource (lib "") (part "2659_1"))
    )
    (comp (ref "D43")
      (value "2659")
      (footprint "2659")
      (description "20 AWG Hook-Up Wire 26/34 White 300V 40.00' _12.19m_")
      (fields (field (name "MF") "Adafruit Industries") (field (name "DIGI-KEY_PART_NUMBER") "2183-2659-ND"))
      (libsource (lib "") (part "2659_1"))
    )
    (comp (ref "D44")
      (value "2659")
      (footprint "2659")
      (description "20 AWG Hook-Up Wire 26/34 White 300V 40.00' _12.19m_")
      (fields (field (name "MF") "Adafruit Industries") (field (name "DIGI-KEY_PART_NUMBER") "2183-2659-ND"))
      (libsource (lib "") (part "2659_1"))
    )
    (comp (ref "D45")
      (value "2659")
      (footprint "2659")
      (description "20 AWG Hook-Up Wire 26/34 White 300V 40.00' _12.19m_")
      (fields (field (name "MF") "Adafruit Industries") (field (name "DIGI-KEY_PART_NUMBER") "2183-2659-ND"))
      (libsource (lib "") (part "2659_1"))
    )
    (comp (ref "D46")
      (value "2659")
      (footprint "2659")
      (description "20 AWG Hook-Up Wire 26/34 White 300V 40.00' _12.19m_")
      (fields (field (name "MF") "Adafruit Industries") (field (name "DIGI-KEY_PART_NUMBER") "2183-2659-ND"))
      (libsource (lib "") (part "2659_1"))
    )
    (comp (ref "D47")
      (value "2659")
      (footprint "2659")
      (description "20 AWG Hook-Up Wire 26/34 White 300V 40.00' _12.19m_")
      (fields (field (name "MF") "Adafruit Industries") (field (name "DIGI-KEY_PART_NUMBER") "2183-2659-ND"))
      (libsource (lib "") (part "2659_1"))
    )
    (comp (ref "D48")
      (value "2659")
      (footprint "2659")
      (description "20 AWG Hook-Up Wire 26/34 White 300V 40.00' _12.19m_")
      (fields (field (name "MF") "Adafruit Industries") (field (name "DIGI-KEY_PART_NUMBER") "2183-2659-ND"))
      (libsource (lib "") (part "2659_1"))
    )
    (comp (ref "D49")
      (value "2659")
      (footprint "2659")
      (description "20 AWG Hook-Up Wire 26/34 White 300V 40.00' _12.19m_")
      (fields (field (name "MF") "Adafruit Industries") (field (name "DIGI-KEY_PART_NUMBER") "2183-2659-ND"))
      (libsource (lib "") (part "2659_1"))
    )
    (comp (ref "D50")
      (value "2659")
      (footprint "2659")
      (description "20 AWG Hook-Up Wire 26/34 White 300V 40.00' _12.19m_")
      (fields (field (name "MF") "Adafruit Industries") (field (name "DIGI-KEY_PART_NUMBER") "2183-2659-ND"))
      (libsource (lib "") (part "2659_1"))
    )
    (comp (ref "D51")
      (value "2659")
      (footprint "2659")
      (description "20 AWG Hook-Up Wire 26/34 White 300V 40.00' _12.19m_")
      (fields (field (name "MF") "Adafruit Industries") (field (name "DIGI-KEY_PART_NUMBER") "2183-2659-ND"))
      (libsource (lib "Michal") (part "2659"))
    )
    (comp (ref "D52")
      (value "2659")
      (footprint "2659")
      (description "20 AWG Hook-Up Wire 26/34 White 300V 40.00' _12.19m_")
      (fields (field (name "MF") "Adafruit Industries") (field (name "DIGI-KEY_PART_NUMBER") "2183-2659-ND"))
      (libsource (lib "Michal") (part "2659"))
    )
    (comp (ref "D53")
      (value "2659")
      (footprint "2659")
      (description "20 AWG Hook-Up Wire 26/34 White 300V 40.00' _12.19m_")
      (fields (field (name "MF") "Adafruit Industries") (field (name "DIGI-KEY_PART_NUMBER") "2183-2659-ND"))
      (libsource (lib "Michal") (part "2659"))
    )
    (comp (ref "D54")
      (value "2659")
      (footprint "2659")
      (description "20 AWG Hook-Up Wire 26/34 White 300V 40.00' _12.19m_")
      (fields (field (name "MF") "Adafruit Industries") (field (name "DIGI-KEY_PART_NUMBER") "2183-2659-ND"))
      (libsource (lib "Michal") (part "2659"))
    )
    (comp (ref "D55")
      (value "2659")
      (footprint "2659")
      (description "20 AWG Hook-Up Wire 26/34 White 300V 40.00' _12.19m_")
      (fields (field (name "MF") "Adafruit Industries") (field (name "DIGI-KEY_PART_NUMBER") "2183-2659-ND"))
      (libsource (lib "Michal") (part "2659"))
    )
    (comp (ref "D56")
      (value "2659")
      (footprint "2659")
      (description "20 AWG Hook-Up Wire 26/34 White 300V 40.00' _12.19m_")
      (fields (field (name "MF") "Adafruit Industries") (field (name "DIGI-KEY_PART_NUMBER") "2183-2659-ND"))
      (libsource (lib "Michal") (part "2659"))
    )
    (comp (ref "D57")
      (value "2659")
      (footprint "2659")
      (description "20 AWG Hook-Up Wire 26/34 White 300V 40.00' _12.19m_")
      (fields (field (name "MF") "Adafruit Industries") (field (name "DIGI-KEY_PART_NUMBER") "2183-2659-ND"))
      (libsource (lib "Michal") (part "2659"))
    )
    (comp (ref "D58")
      (value "2659")
      (footprint "2659")
      (description "20 AWG Hook-Up Wire 26/34 White 300V 40.00' _12.19m_")
      (fields (field (name "MF") "Adafruit Industries") (field (name "DIGI-KEY_PART_NUMBER") "2183-2659-ND"))
      (libsource (lib "Michal") (part "2659"))
    )
    (comp (ref "D59")
      (value "2659")
      (footprint "2659")
      (description "20 AWG Hook-Up Wire 26/34 White 300V 40.00' _12.19m_")
      (fields (field (name "MF") "Adafruit Industries") (field (name "DIGI-KEY_PART_NUMBER") "2183-2659-ND"))
      (libsource (lib "Michal") (part "2659"))
    )
    (comp (ref "D60")
      (value "2659")
      (footprint "2659")
      (description "20 AWG Hook-Up Wire 26/34 White 300V 40.00' _12.19m_")
      (fields (field (name "MF") "Adafruit Industries") (field (name "DIGI-KEY_PART_NUMBER") "2183-2659-ND"))
      (libsource (lib "Michal") (part "2659"))
    )
    (comp (ref "D61")
      (value "2659")
      (footprint "2659")
      (description "20 AWG Hook-Up Wire 26/34 White 300V 40.00' _12.19m_")
      (fields (field (name "MF") "Adafruit Industries") (field (name "DIGI-KEY_PART_NUMBER") "2183-2659-ND"))
      (libsource (lib "") (part "2659_1"))
    )
    (comp (ref "D62")
      (value "2659")
      (footprint "2659")
      (description "20 AWG Hook-Up Wire 26/34 White 300V 40.00' _12.19m_")
      (fields (field (name "MF") "Adafruit Industries") (field (name "DIGI-KEY_PART_NUMBER") "2183-2659-ND"))
      (libsource (lib "") (part "2659_1"))
    )
    (comp (ref "D63")
      (value "2659")
      (footprint "2659")
      (description "20 AWG Hook-Up Wire 26/34 White 300V 40.00' _12.19m_")
      (fields (field (name "MF") "Adafruit Industries") (field (name "DIGI-KEY_PART_NUMBER") "2183-2659-ND"))
      (libsource (lib "") (part "2659_1"))
    )
    (comp (ref "D64")
      (value "2659")
      (footprint "2659")
      (description "20 AWG Hook-Up Wire 26/34 White 300V 40.00' _12.19m_")
      (fields (field (name "MF") "Adafruit Industries") (field (name "DIGI-KEY_PART_NUMBER") "2183-2659-ND"))
      (libsource (lib "") (part "2659_1"))
    )
    (comp (ref "D65")
      (value "2659")
      (footprint "2659")
      (description "20 AWG Hook-Up Wire 26/34 White 300V 40.00' _12.19m_")
      (fields (field (name "MF") "Adafruit Industries") (field (name "DIGI-KEY_PART_NUMBER") "2183-2659-ND"))
      (libsource (lib "") (part "2659_1"))
    )
    (comp (ref "D66")
      (value "2659")
      (footprint "2659")
      (description "20 AWG Hook-Up Wire 26/34 White 300V 40.00' _12.19m_")
      (fields (field (name "MF") "Adafruit Industries") (field (name "DIGI-KEY_PART_NUMBER") "2183-2659-ND"))
      (libsource (lib "") (part "2659_1"))
    )
    (comp (ref "D67")
      (value "2659")
      (footprint "2659")
      (description "20 AWG Hook-Up Wire 26/34 White 300V 40.00' _12.19m_")
      (fields (field (name "MF") "Adafruit Industries") (field (name "DIGI-KEY_PART_NUMBER") "2183-2659-ND"))
      (libsource (lib "") (part "2659_1"))
    )
    (comp (ref "D68")
      (value "2659")
      (footprint "2659")
      (description "20 AWG Hook-Up Wire 26/34 White 300V 40.00' _12.19m_")
      (fields (field (name "MF") "Adafruit Industries") (field (name "DIGI-KEY_PART_NUMBER") "2183-2659-ND"))
      (libsource (lib "") (part "2659_1"))
    )
    (comp (ref "D69")
      (value "2659")
      (footprint "2659")
      (description "20 AWG Hook-Up Wire 26/34 White 300V 40.00' _12.19m_")
      (fields (field (name "MF") "Adafruit Industries") (field (name "DIGI-KEY_PART_NUMBER") "2183-2659-ND"))
      (libsource (lib "") (part "2659_1"))
    )
    (comp (ref "D70")
      (value "2659")
      (footprint "2659")
      (description "20 AWG Hook-Up Wire 26/34 White 300V 40.00' _12.19m_")
      (fields (field (name "MF") "Adafruit Industries") (field (name "DIGI-KEY_PART_NUMBER") "2183-2659-ND"))
      (libsource (lib "") (part "2659_1"))
    )
    (comp (ref "D71")
      (value "2659")
      (footprint "2659")
      (description "20 AWG Hook-Up Wire 26/34 White 300V 40.00' _12.19m_")
      (fields (field (name "MF") "Adafruit Industries") (field (name "DIGI-KEY_PART_NUMBER") "2183-2659-ND"))
      (libsource (lib "Michal") (part "2659"))
    )
    (comp (ref "D72")
      (value "2659")
      (footprint "2659")
      (description "20 AWG Hook-Up Wire 26/34 White 300V 40.00' _12.19m_")
      (fields (field (name "MF") "Adafruit Industries") (field (name "DIGI-KEY_PART_NUMBER") "2183-2659-ND"))
      (libsource (lib "Michal") (part "2659"))
    )
    (comp (ref "D73")
      (value "2659")
      (footprint "2659")
      (description "20 AWG Hook-Up Wire 26/34 White 300V 40.00' _12.19m_")
      (fields (field (name "MF") "Adafruit Industries") (field (name "DIGI-KEY_PART_NUMBER") "2183-2659-ND"))
      (libsource (lib "Michal") (part "2659"))
    )
    (comp (ref "D74")
      (value "2659")
      (footprint "2659")
      (description "20 AWG Hook-Up Wire 26/34 White 300V 40.00' _12.19m_")
      (fields (field (name "MF") "Adafruit Industries") (field (name "DIGI-KEY_PART_NUMBER") "2183-2659-ND"))
      (libsource (lib "Michal") (part "2659"))
    )
    (comp (ref "D75")
      (value "2659")
      (footprint "2659")
      (description "20 AWG Hook-Up Wire 26/34 White 300V 40.00' _12.19m_")
      (fields (field (name "MF") "Adafruit Industries") (field (name "DIGI-KEY_PART_NUMBER") "2183-2659-ND"))
      (libsource (lib "Michal") (part "2659"))
    )
    (comp (ref "D76")
      (value "2659")
      (footprint "2659")
      (description "20 AWG Hook-Up Wire 26/34 White 300V 40.00' _12.19m_")
      (fields (field (name "MF") "Adafruit Industries") (field (name "DIGI-KEY_PART_NUMBER") "2183-2659-ND"))
      (libsource (lib "Michal") (part "2659"))
    )
    (comp (ref "D77")
      (value "2659")
      (footprint "2659")
      (description "20 AWG Hook-Up Wire 26/34 White 300V 40.00' _12.19m_")
      (fields (field (name "MF") "Adafruit Industries") (field (name "DIGI-KEY_PART_NUMBER") "2183-2659-ND"))
      (libsource (lib "Michal") (part "2659"))
    )
    (comp (ref "D78")
      (value "2659")
      (footprint "2659")
      (description "20 AWG Hook-Up Wire 26/34 White 300V 40.00' _12.19m_")
      (fields (field (name "MF") "Adafruit Industries") (field (name "DIGI-KEY_PART_NUMBER") "2183-2659-ND"))
      (libsource (lib "Michal") (part "2659"))
    )
    (comp (ref "D79")
      (value "2659")
      (footprint "2659")
      (description "20 AWG Hook-Up Wire 26/34 White 300V 40.00' _12.19m_")
      (fields (field (name "MF") "Adafruit Industries") (field (name "DIGI-KEY_PART_NUMBER") "2183-2659-ND"))
      (libsource (lib "Michal") (part "2659"))
    )
    (comp (ref "D80")
      (value "2659")
      (footprint "2659")
      (description "20 AWG Hook-Up Wire 26/34 White 300V 40.00' _12.19m_")
      (fields (field (name "MF") "Adafruit Industries") (field (name "DIGI-KEY_PART_NUMBER") "2183-2659-ND"))
      (libsource (lib "Michal") (part "2659"))
    )
    (comp (ref "D81")
      (value "2659")
      (footprint "2659")
      (description "20 AWG Hook-Up Wire 26/34 White 300V 40.00' _12.19m_")
      (fields (field (name "MF") "Adafruit Industries") (field (name "DIGI-KEY_PART_NUMBER") "2183-2659-ND"))
      (libsource (lib "") (part "2659_1"))
    )
    (comp (ref "D82")
      (value "2659")
      (footprint "2659")
      (description "20 AWG Hook-Up Wire 26/34 White 300V 40.00' _12.19m_")
      (fields (field (name "MF") "Adafruit Industries") (field (name "DIGI-KEY_PART_NUMBER") "2183-2659-ND"))
      (libsource (lib "") (part "2659_1"))
    )
    (comp (ref "D83")
      (value "2659")
      (footprint "2659")
      (description "20 AWG Hook-Up Wire 26/34 White 300V 40.00' _12.19m_")
      (fields (field (name "MF") "Adafruit Industries") (field (name "DIGI-KEY_PART_NUMBER") "2183-2659-ND"))
      (libsource (lib "") (part "2659_1"))
    )
    (comp (ref "D84")
      (value "2659")
      (footprint "2659")
      (description "20 AWG Hook-Up Wire 26/34 White 300V 40.00' _12.19m_")
      (fields (field (name "MF") "Adafruit Industries") (field (name "DIGI-KEY_PART_NUMBER") "2183-2659-ND"))
      (libsource (lib "") (part "2659_1"))
    )
    (comp (ref "D85")
      (value "2659")
      (footprint "2659")
      (description "20 AWG Hook-Up Wire 26/34 White 300V 40.00' _12.19m_")
      (fields (field (name "MF") "Adafruit Industries") (field (name "DIGI-KEY_PART_NUMBER") "2183-2659-ND"))
      (libsource (lib "") (part "2659_1"))
    )
    (comp (ref "D86")
      (value "2659")
      (footprint "2659")
      (description "20 AWG Hook-Up Wire 26/34 White 300V 40.00' _12.19m_")
      (fields (field (name "MF") "Adafruit Industries") (field (name "DIGI-KEY_PART_NUMBER") "2183-2659-ND"))
      (libsource (lib "") (part "2659_1"))
    )
    (comp (ref "D87")
      (value "2659")
      (footprint "2659")
      (description "20 AWG Hook-Up Wire 26/34 White 300V 40.00' _12.19m_")
      (fields (field (name "MF") "Adafruit Industries") (field (name "DIGI-KEY_PART_NUMBER") "2183-2659-ND"))
      (libsource (lib "") (part "2659_1"))
    )
    (comp (ref "D88")
      (value "2659")
      (footprint "2659")
      (description "20 AWG Hook-Up Wire 26/34 White 300V 40.00' _12.19m_")
      (fields (field (name "MF") "Adafruit Industries") (field (name "DIGI-KEY_PART_NUMBER") "2183-2659-ND"))
      (libsource (lib "") (part "2659_1"))
    )
    (comp (ref "D89")
      (value "2659")
      (footprint "2659")
      (description "20 AWG Hook-Up Wire 26/34 White 300V 40.00' _12.19m_")
      (fields (field (name "MF") "Adafruit Industries") (field (name "DIGI-KEY_PART_NUMBER") "2183-2659-ND"))
      (libsource (lib "") (part "2659_1"))
    )
    (comp (ref "D90")
      (value "2659")
      (footprint "2659")
      (description "20 AWG Hook-Up Wire 26/34 White 300V 40.00' _12.19m_")
      (fields (field (name "MF") "Adafruit Industries") (field (name "DIGI-KEY_PART_NUMBER") "2183-2659-ND"))
      (libsource (lib "") (part "2659_1"))
    )
    (comp (ref "D91")
      (value "2659")
      (footprint "2659")
      (description "20 AWG Hook-Up Wire 26/34 White 300V 40.00' _12.19m_")
      (fields (field (name "MF") "Adafruit Industries") (field (name "DIGI-KEY_PART_NUMBER") "2183-2659-ND"))
      (libsource (lib "Michal") (part "2659"))
    )
    (comp (ref "D92")
      (value "2659")
      (footprint "2659")
      (description "20 AWG Hook-Up Wire 26/34 White 300V 40.00' _12.19m_")
      (fields (field (name "MF") "Adafruit Industries") (field (name "DIGI-KEY_PART_NUMBER") "2183-2659-ND"))
      (libsource (lib "Michal") (part "2659"))
    )
    (comp (ref "D93")
      (value "2659")
      (footprint "2659")
      (description "20 AWG Hook-Up Wire 26/34 White 300V 40.00' _12.19m_")
      (fields (field (name "MF") "Adafruit Industries") (field (name "DIGI-KEY_PART_NUMBER") "2183-2659-ND"))
      (libsource (lib "Michal") (part "2659"))
    )
    (comp (ref "D94")
      (value "2659")
      (footprint "2659")
      (description "20 AWG Hook-Up Wire 26/34 White 300V 40.00' _12.19m_")
      (fields (field (name "MF") "Adafruit Industries") (field (name "DIGI-KEY_PART_NUMBER") "2183-2659-ND"))
      (libsource (lib "Michal") (part "2659"))
    )
    (comp (ref "D95")
      (value "2659")
      (footprint "2659")
      (description "20 AWG Hook-Up Wire 26/34 White 300V 40.00' _12.19m_")
      (fields (field (name "MF") "Adafruit Industries") (field (name "DIGI-KEY_PART_NUMBER") "2183-2659-ND"))
      (libsource (lib "Michal") (part "2659"))
    )
    (comp (ref "D96")
      (value "2659")
      (footprint "2659")
      (description "20 AWG Hook-Up Wire 26/34 White 300V 40.00' _12.19m_")
      (fields (field (name "MF") "Adafruit Industries") (field (name "DIGI-KEY_PART_NUMBER") "2183-2659-ND"))
      (libsource (lib "Michal") (part "2659"))
    )
    (comp (ref "D97")
      (value "2659")
      (footprint "2659")
      (description "20 AWG Hook-Up Wire 26/34 White 300V 40.00' _12.19m_")
      (fields (field (name "MF") "Adafruit Industries") (field (name "DIGI-KEY_PART_NUMBER") "2183-2659-ND"))
      (libsource (lib "Michal") (part "2659"))
    )
    (comp (ref "D98")
      (value "2659")
      (footprint "2659")
      (description "20 AWG Hook-Up Wire 26/34 White 300V 40.00' _12.19m_")
      (fields (field (name "MF") "Adafruit Industries") (field (name "DIGI-KEY_PART_NUMBER") "2183-2659-ND"))
      (libsource (lib "Michal") (part "2659"))
    )
    (comp (ref "D99")
      (value "2659")
      (footprint "2659")
      (description "20 AWG Hook-Up Wire 26/34 White 300V 40.00' _12.19m_")
      (fields (field (name "MF") "Adafruit Industries") (field (name "DIGI-KEY_PART_NUMBER") "2183-2659-ND"))
      (libsource (lib "Michal") (part "2659"))
    )
    (comp (ref "D100")
      (value "2659")
      (footprint "2659")
      (description "20 AWG Hook-Up Wire 26/34 White 300V 40.00' _12.19m_")
      (fields (field (name "MF") "Adafruit Industries") (field (name "DIGI-KEY_PART_NUMBER") "2183-2659-ND"))
      (libsource (lib "Michal") (part "2659"))
    )
    (comp (ref "J1")
      (value "874270602")
      (footprint "MOLEX_874270602")
      (libsource (lib "Michal") (part "874270602"))
    )
  )
  (nets
    (net (code "1") (name "+5") (class "Default")
      (node (ref "C1") (pin "1") (pinfunction "1_1") (pintype "passive"))
      (node (ref "C10") (pin "1") (pinfunction "1_1") (pintype "passive"))
      (node (ref "C100") (pin "1") (pinfunction "1_1") (pintype "passive"))
      (node (ref "C11") (pin "1") (pinfunction "1_1") (pintype "passive"))
      (node (ref "C12") (pin "1") (pinfunction "1_1") (pintype "passive"))
      (node (ref "C13") (pin "1") (pinfunction "1_1") (pintype "passive"))
      (node (ref "C14") (pin "1") (pinfunction "1_1") (pintype "passive"))
      (node (ref "C15") (pin "1") (pinfunction "1_1") (pintype "passive"))
      (node (ref "C16") (pin "1") (pinfunction "1_1") (pintype "passive"))
      (node (ref "C17") (pin "1") (pinfunction "1_1") (pintype "passive"))
      (node (ref "C18") (pin "1") (pinfunction "1_1") (pintype "passive"))
      (node (ref "C19") (pin "1") (pinfunction "1_1") (pintype "passive"))
      (node (ref "C2") (pin "1") (pinfunction "1_1") (pintype "passive"))
      (node (ref "C20") (pin "1") (pinfunction "1_1") (pintype "passive"))
      (node (ref "C21") (pin "1") (pinfunction "1_1") (pintype "passive"))
      (node (ref "C22") (pin "1") (pinfunction "1_1") (pintype "passive"))
      (node (ref "C23") (pin "1") (pinfunction "1_1") (pintype "passive"))
      (node (ref "C24") (pin "1") (pinfunction "1_1") (pintype "passive"))
      (node (ref "C25") (pin "1") (pinfunction "1_1") (pintype "passive"))
      (node (ref "C26") (pin "1") (pinfunction "1_1") (pintype "passive"))
      (node (ref "C27") (pin "1") (pinfunction "1_1") (pintype "passive"))
      (node (ref "C28") (pin "1") (pinfunction "1_1") (pintype "passive"))
      (node (ref "C29") (pin "1") (pinfunction "1_1") (pintype "passive"))
      (node (ref "C3") (pin "1") (pinfunction "1_1") (pintype "passive"))
      (node (ref "C30") (pin "1") (pinfunction "1_1") (pintype "passive"))
      (node (ref "C31") (pin "1") (pinfunction "1_1") (pintype "passive"))
      (node (ref "C32") (pin "1") (pinfunction "1_1") (pintype "passive"))
      (node (ref "C33") (pin "1") (pinfunction "1_1") (pintype "passive"))
      (node (ref "C34") (pin "1") (pinfunction "1_1") (pintype "passive"))
      (node (ref "C35") (pin "1") (pinfunction "1_1") (pintype "passive"))
      (node (ref "C36") (pin "1") (pinfunction "1_1") (pintype "passive"))
      (node (ref "C37") (pin "1") (pinfunction "1_1") (pintype "passive"))
      (node (ref "C38") (pin "1") (pinfunction "1_1") (pintype "passive"))
      (node (ref "C39") (pin "1") (pinfunction "1_1") (pintype "passive"))
      (node (ref "C4") (pin "1") (pinfunction "1_1") (pintype "passive"))
      (node (ref "C40") (pin "1") (pinfunction "1_1") (pintype "passive"))
      (node (ref "C41") (pin "1") (pinfunction "1_1") (pintype "passive"))
      (node (ref "C42") (pin "1") (pinfunction "1_1") (pintype "passive"))
      (node (ref "C43") (pin "1") (pinfunction "1_1") (pintype "passive"))
      (node (ref "C44") (pin "1") (pinfunction "1_1") (pintype "passive"))
      (node (ref "C45") (pin "1") (pinfunction "1_1") (pintype "passive"))
      (node (ref "C46") (pin "1") (pinfunction "1_1") (pintype "passive"))
      (node (ref "C47") (pin "1") (pinfunction "1_1") (pintype "passive"))
      (node (ref "C48") (pin "1") (pinfunction "1_1") (pintype "passive"))
      (node (ref "C49") (pin "1") (pinfunction "1_1") (pintype "passive"))
      (node (ref "C5") (pin "1") (pinfunction "1_1") (pintype "passive"))
      (node (ref "C50") (pin "1") (pinfunction "1_1") (pintype "passive"))
      (node (ref "C51") (pin "1") (pinfunction "1_1") (pintype "passive"))
      (node (ref "C52") (pin "1") (pinfunction "1_1") (pintype "passive"))
      (node (ref "C53") (pin "1") (pinfunction "1_1") (pintype "passive"))
      (node (ref "C54") (pin "1") (pinfunction "1_1") (pintype "passive"))
      (node (ref "C55") (pin "1") (pinfunction "1_1") (pintype "passive"))
      (node (ref "C56") (pin "1") (pinfunction "1_1") (pintype "passive"))
      (node (ref "C57") (pin "1") (pinfunction "1_1") (pintype "passive"))
      (node (ref "C58") (pin "1") (pinfunction "1_1") (pintype "passive"))
      (node (ref "C59") (pin "1") (pinfunction "1_1") (pintype "passive"))
      (node (ref "C6") (pin "1") (pinfunction "1_1") (pintype "passive"))
      (node (ref "C60") (pin "1") (pinfunction "1_1") (pintype "passive"))
      (node (ref "C61") (pin "1") (pinfunction "1_1") (pintype "passive"))
      (node (ref "C62") (pin "1") (pinfunction "1_1") (pintype "passive"))
      (node (ref "C63") (pin "1") (pinfunction "1_1") (pintype "passive"))
      (node (ref "C64") (pin "1") (pinfunction "1_1") (pintype "passive"))
      (node (ref "C65") (pin "1") (pinfunction "1_1") (pintype "passive"))
      (node (ref "C66") (pin "1") (pinfunction "1_1") (pintype "passive"))
      (node (ref "C67") (pin "1") (pinfunction "1_1") (pintype "passive"))
      (node (ref "C68") (pin "1") (pinfunction "1_1") (pintype "passive"))
      (node (ref "C69") (pin "1") (pinfunction "1_1") (pintype "passive"))
      (node (ref "C7") (pin "1") (pinfunction "1_1") (pintype "passive"))
      (node (ref "C70") (pin "1") (pinfunction "1_1") (pintype "passive"))
      (node (ref "C71") (pin "1") (pinfunction "1_1") (pintype "passive"))
      (node (ref "C72") (pin "1") (pinfunction "1_1") (pintype "passive"))
      (node (ref "C73") (pin "1") (pinfunction "1_1") (pintype "passive"))
      (node (ref "C74") (pin "1") (pinfunction "1_1") (pintype "passive"))
      (node (ref "C75") (pin "1") (pinfunction "1_1") (pintype "passive"))
      (node (ref "C76") (pin "1") (pinfunction "1_1") (pintype "passive"))
      (node (ref "C77") (pin "1") (pinfunction "1_1") (pintype "passive"))
      (node (ref "C78") (pin "1") (pinfunction "1_1") (pintype "passive"))
      (node (ref "C79") (pin "1") (pinfunction "1_1") (pintype "passive"))
      (node (ref "C8") (pin "1") (pinfunction "1_1") (pintype "passive"))
      (node (ref "C80") (pin "1") (pinfunction "1_1") (pintype "passive"))
      (node (ref "C81") (pin "1") (pinfunction "1_1") (pintype "passive"))
      (node (ref "C82") (pin "1") (pinfunction "1_1") (pintype "passive"))
      (node (ref "C83") (pin "1") (pinfunction "1_1") (pintype "passive"))
      (node (ref "C84") (pin "1") (pinfunction "1_1") (pintype "passive"))
      (node (ref "C85") (pin "1") (pinfunction "1_1") (pintype "passive"))
      (node (ref "C86") (pin "1") (pinfunction "1_1") (pintype "passive"))
      (node (ref "C87") (pin "1") (pinfunction "1_1") (pintype "passive"))
      (node (ref "C88") (pin "1") (pinfunction "1_1") (pintype "passive"))
      (node (ref "C89") (pin "1") (pinfunction "1_1") (pintype "passive"))
      (node (ref "C9") (pin "1") (pinfunction "1_1") (pintype "passive"))
      (node (ref "C90") (pin "1") (pinfunction "1_1") (pintype "passive"))
      (node (ref "C91") (pin "1") (pinfunction "1_1") (pintype "passive"))
      (node (ref "C92") (pin "1") (pinfunction "1_1") (pintype "passive"))
      (node (ref "C93") (pin "1") (pinfunction "1_1") (pintype "passive"))
      (node (ref "C94") (pin "1") (pinfunction "1_1") (pintype "passive"))
      (node (ref "C95") (pin "1") (pinfunction "1_1") (pintype "passive"))
      (node (ref "C96") (pin "1") (pinfunction "1_1") (pintype "passive"))
      (node (ref "C97") (pin "1") (pinfunction "1_1") (pintype "passive"))
      (node (ref "C98") (pin "1") (pinfunction "1_1") (pintype "passive"))
      (node (ref "C99") (pin "1") (pinfunction "1_1") (pintype "passive"))
      (node (ref "D1") (pin "4") (pinfunction "VDD_4") (pintype "power_in"))
      (node (ref "D10") (pin "4") (pinfunction "VDD_4") (pintype "power_in"))
      (node (ref "D100") (pin "4") (pinfunction "VDD_4") (pintype "power_in"))
      (node (ref "D11") (pin "4") (pinfunction "VDD_4") (pintype "power_in"))
      (node (ref "D12") (pin "4") (pinfunction "VDD_4") (pintype "power_in"))
      (node (ref "D13") (pin "4") (pinfunction "VDD_4") (pintype "power_in"))
      (node (ref "D14") (pin "4") (pinfunction "VDD_4") (pintype "power_in"))
      (node (ref "D15") (pin "4") (pinfunction "VDD_4") (pintype "power_in"))
      (node (ref "D16") (pin "4") (pinfunction "VDD_4") (pintype "power_in"))
      (node (ref "D17") (pin "4") (pinfunction "VDD_4") (pintype "power_in"))
      (node (ref "D18") (pin "4") (pinfunction "VDD_4") (pintype "power_in"))
      (node (ref "D19") (pin "4") (pinfunction "VDD_4") (pintype "power_in"))
      (node (ref "D2") (pin "4") (pinfunction "VDD_4") (pintype "power_in"))
      (node (ref "D20") (pin "4") (pinfunction "VDD_4") (pintype "power_in"))
      (node (ref "D21") (pin "4") (pinfunction "VDD_4") (pintype "power_in"))
      (node (ref "D22") (pin "4") (pinfunction "VDD_4") (pintype "power_in"))
      (node (ref "D23") (pin "4") (pinfunction "VDD_4") (pintype "power_in"))
      (node (ref "D24") (pin "4") (pinfunction "VDD_4") (pintype "power_in"))
      (node (ref "D25") (pin "4") (pinfunction "VDD_4") (pintype "power_in"))
      (node (ref "D26") (pin "4") (pinfunction "VDD_4") (pintype "power_in"))
      (node (ref "D27") (pin "4") (pinfunction "VDD_4") (pintype "power_in"))
      (node (ref "D28") (pin "4") (pinfunction "VDD_4") (pintype "power_in"))
      (node (ref "D29") (pin "4") (pinfunction "VDD_4") (pintype "power_in"))
      (node (ref "D3") (pin "4") (pinfunction "VDD_4") (pintype "power_in"))
      (node (ref "D30") (pin "4") (pinfunction "VDD_4") (pintype "power_in"))
      (node (ref "D31") (pin "4") (pinfunction "VDD_4") (pintype "power_in"))
      (node (ref "D32") (pin "4") (pinfunction "VDD_4") (pintype "power_in"))
      (node (ref "D33") (pin "4") (pinfunction "VDD_4") (pintype "power_in"))
      (node (ref "D34") (pin "4") (pinfunction "VDD_4") (pintype "power_in"))
      (node (ref "D35") (pin "4") (pinfunction "VDD_4") (pintype "power_in"))
      (node (ref "D36") (pin "4") (pinfunction "VDD_4") (pintype "power_in"))
      (node (ref "D37") (pin "4") (pinfunction "VDD_4") (pintype "power_in"))
      (node (ref "D38") (pin "4") (pinfunction "VDD_4") (pintype "power_in"))
      (node (ref "D39") (pin "4") (pinfunction "VDD_4") (pintype "power_in"))
      (node (ref "D4") (pin "4") (pinfunction "VDD_4") (pintype "power_in"))
      (node (ref "D40") (pin "4") (pinfunction "VDD_4") (pintype "power_in"))
      (node (ref "D41") (pin "4") (pinfunction "VDD_4") (pintype "power_in"))
      (node (ref "D42") (pin "4") (pinfunction "VDD_4") (pintype "power_in"))
      (node (ref "D43") (pin "4") (pinfunction "VDD_4") (pintype "power_in"))
      (node (ref "D44") (pin "4") (pinfunction "VDD_4") (pintype "power_in"))
      (node (ref "D45") (pin "4") (pinfunction "VDD_4") (pintype "power_in"))
      (node (ref "D46") (pin "4") (pinfunction "VDD_4") (pintype "power_in"))
      (node (ref "D47") (pin "4") (pinfunction "VDD_4") (pintype "power_in"))
      (node (ref "D48") (pin "4") (pinfunction "VDD_4") (pintype "power_in"))
      (node (ref "D49") (pin "4") (pinfunction "VDD_4") (pintype "power_in"))
      (node (ref "D5") (pin "4") (pinfunction "VDD_4") (pintype "power_in"))
      (node (ref "D50") (pin "4") (pinfunction "VDD_4") (pintype "power_in"))
      (node (ref "D51") (pin "4") (pinfunction "VDD_4") (pintype "power_in"))
      (node (ref "D52") (pin "4") (pinfunction "VDD_4") (pintype "power_in"))
      (node (ref "D53") (pin "4") (pinfunction "VDD_4") (pintype "power_in"))
      (node (ref "D54") (pin "4") (pinfunction "VDD_4") (pintype "power_in"))
      (node (ref "D55") (pin "4") (pinfunction "VDD_4") (pintype "power_in"))
      (node (ref "D56") (pin "4") (pinfunction "VDD_4") (pintype "power_in"))
      (node (ref "D57") (pin "4") (pinfunction "VDD_4") (pintype "power_in"))
      (node (ref "D58") (pin "4") (pinfunction "VDD_4") (pintype "power_in"))
      (node (ref "D59") (pin "4") (pinfunction "VDD_4") (pintype "power_in"))
      (node (ref "D6") (pin "4") (pinfunction "VDD_4") (pintype "power_in"))
      (node (ref "D60") (pin "4") (pinfunction "VDD_4") (pintype "power_in"))
      (node (ref "D61") (pin "4") (pinfunction "VDD_4") (pintype "power_in"))
      (node (ref "D62") (pin "4") (pinfunction "VDD_4") (pintype "power_in"))
      (node (ref "D63") (pin "4") (pinfunction "VDD_4") (pintype "power_in"))
      (node (ref "D64") (pin "4") (pinfunction "VDD_4") (pintype "power_in"))
      (node (ref "D65") (pin "4") (pinfunction "VDD_4") (pintype "power_in"))
      (node (ref "D66") (pin "4") (pinfunction "VDD_4") (pintype "power_in"))
      (node (ref "D67") (pin "4") (pinfunction "VDD_4") (pintype "power_in"))
      (node (ref "D68") (pin "4") (pinfunction "VDD_4") (pintype "power_in"))
      (node (ref "D69") (pin "4") (pinfunction "VDD_4") (pintype "power_in"))
      (node (ref "D7") (pin "4") (pinfunction "VDD_4") (pintype "power_in"))
      (node (ref "D70") (pin "4") (pinfunction "VDD_4") (pintype "power_in"))
      (node (ref "D71") (pin "4") (pinfunction "VDD_4") (pintype "power_in"))
      (node (ref "D72") (pin "4") (pinfunction "VDD_4") (pintype "power_in"))
      (node (ref "D73") (pin "4") (pinfunction "VDD_4") (pintype "power_in"))
      (node (ref "D74") (pin "4") (pinfunction "VDD_4") (pintype "power_in"))
      (node (ref "D75") (pin "4") (pinfunction "VDD_4") (pintype "power_in"))
      (node (ref "D76") (pin "4") (pinfunction "VDD_4") (pintype "power_in"))
      (node (ref "D77") (pin "4") (pinfunction "VDD_4") (pintype "power_in"))
      (node (ref "D78") (pin "4") (pinfunction "VDD_4") (pintype "power_in"))
      (node (ref "D79") (pin "4") (pinfunction "VDD_4") (pintype "power_in"))
      (node (ref "D8") (pin "4") (pinfunction "VDD_4") (pintype "power_in"))
      (node (ref "D80") (pin "4") (pinfunction "VDD_4") (pintype "power_in"))
      (node (ref "D81") (pin "4") (pinfunction "VDD_4") (pintype "power_in"))
      (node (ref "D82") (pin "4") (pinfunction "VDD_4") (pintype "power_in"))
      (node (ref "D83") (pin "4") (pinfunction "VDD_4") (pintype "power_in"))
      (node (ref "D84") (pin "4") (pinfunction "VDD_4") (pintype "power_in"))
      (node (ref "D85") (pin "4") (pinfunction "VDD_4") (pintype "power_in"))
      (node (ref "D86") (pin "4") (pinfunction "VDD_4") (pintype "power_in"))
      (node (ref "D87") (pin "4") (pinfunction "VDD_4") (pintype "power_in"))
      (node (ref "D88") (pin "4") (pinfunction "VDD_4") (pintype "power_in"))
      (node (ref "D89") (pin "4") (pinfunction "VDD_4") (pintype "power_in"))
      (node (ref "D9") (pin "4") (pinfunction "VDD_4") (pintype "power_in"))
      (node (ref "D90") (pin "4") (pinfunction "VDD_4") (pintype "power_in"))
      (node (ref "D91") (pin "4") (pinfunction "VDD_4") (pintype "power_in"))
      (node (ref "D92") (pin "4") (pinfunction "VDD_4") (pintype "power_in"))
      (node (ref "D93") (pin "4") (pinfunction "VDD_4") (pintype "power_in"))
      (node (ref "D94") (pin "4") (pinfunction "VDD_4") (pintype "power_in"))
      (node (ref "D95") (pin "4") (pinfunction "VDD_4") (pintype "power_in"))
      (node (ref "D96") (pin "4") (pinfunction "VDD_4") (pintype "power_in"))
      (node (ref "D97") (pin "4") (pinfunction "VDD_4") (pintype "power_in"))
      (node (ref "D98") (pin "4") (pinfunction "VDD_4") (pintype "power_in"))
      (node (ref "D99") (pin "4") (pinfunction "VDD_4") (pintype "power_in"))
      (node (ref "J1") (pin "4") (pinfunction "4_4") (pintype "passive"))
    )
    (net (code "2") (name "GND") (class "Default")
      (node (ref "C1") (pin "2") (pinfunction "2_2") (pintype "passive"))
      (node (ref "C10") (pin "2") (pinfunction "2_2") (pintype "passive"))
      (node (ref "C100") (pin "2") (pinfunction "2_2") (pintype "passive"))
      (node (ref "C11") (pin "2") (pinfunction "2_2") (pintype "passive"))
      (node (ref "C12") (pin "2") (pinfunction "2_2") (pintype "passive"))
      (node (ref "C13") (pin "2") (pinfunction "2_2") (pintype "passive"))
      (node (ref "C14") (pin "2") (pinfunction "2_2") (pintype "passive"))
      (node (ref "C15") (pin "2") (pinfunction "2_2") (pintype "passive"))
      (node (ref "C16") (pin "2") (pinfunction "2_2") (pintype "passive"))
      (node (ref "C17") (pin "2") (pinfunction "2_2") (pintype "passive"))
      (node (ref "C18") (pin "2") (pinfunction "2_2") (pintype "passive"))
      (node (ref "C19") (pin "2") (pinfunction "2_2") (pintype "passive"))
      (node (ref "C2") (pin "2") (pinfunction "2_2") (pintype "passive"))
      (node (ref "C20") (pin "2") (pinfunction "2_2") (pintype "passive"))
      (node (ref "C21") (pin "2") (pinfunction "2_2") (pintype "passive"))
      (node (ref "C22") (pin "2") (pinfunction "2_2") (pintype "passive"))
      (node (ref "C23") (pin "2") (pinfunction "2_2") (pintype "passive"))
      (node (ref "C24") (pin "2") (pinfunction "2_2") (pintype "passive"))
      (node (ref "C25") (pin "2") (pinfunction "2_2") (pintype "passive"))
      (node (ref "C26") (pin "2") (pinfunction "2_2") (pintype "passive"))
      (node (ref "C27") (pin "2") (pinfunction "2_2") (pintype "passive"))
      (node (ref "C28") (pin "2") (pinfunction "2_2") (pintype "passive"))
      (node (ref "C29") (pin "2") (pinfunction "2_2") (pintype "passive"))
      (node (ref "C3") (pin "2") (pinfunction "2_2") (pintype "passive"))
      (node (ref "C30") (pin "2") (pinfunction "2_2") (pintype "passive"))
      (node (ref "C31") (pin "2") (pinfunction "2_2") (pintype "passive"))
      (node (ref "C32") (pin "2") (pinfunction "2_2") (pintype "passive"))
      (node (ref "C33") (pin "2") (pinfunction "2_2") (pintype "passive"))
      (node (ref "C34") (pin "2") (pinfunction "2_2") (pintype "passive"))
      (node (ref "C35") (pin "2") (pinfunction "2_2") (pintype "passive"))
      (node (ref "C36") (pin "2") (pinfunction "2_2") (pintype "passive"))
      (node (ref "C37") (pin "2") (pinfunction "2_2") (pintype "passive"))
      (node (ref "C38") (pin "2") (pinfunction "2_2") (pintype "passive"))
      (node (ref "C39") (pin "2") (pinfunction "2_2") (pintype "passive"))
      (node (ref "C4") (pin "2") (pinfunction "2_2") (pintype "passive"))
      (node (ref "C40") (pin "2") (pinfunction "2_2") (pintype "passive"))
      (node (ref "C41") (pin "2") (pinfunction "2_2") (pintype "passive"))
      (node (ref "C42") (pin "2") (pinfunction "2_2") (pintype "passive"))
      (node (ref "C43") (pin "2") (pinfunction "2_2") (pintype "passive"))
      (node (ref "C44") (pin "2") (pinfunction "2_2") (pintype "passive"))
      (node (ref "C45") (pin "2") (pinfunction "2_2") (pintype "passive"))
      (node (ref "C46") (pin "2") (pinfunction "2_2") (pintype "passive"))
      (node (ref "C47") (pin "2") (pinfunction "2_2") (pintype "passive"))
      (node (ref "C48") (pin "2") (pinfunction "2_2") (pintype "passive"))
      (node (ref "C49") (pin "2") (pinfunction "2_2") (pintype "passive"))
      (node (ref "C5") (pin "2") (pinfunction "2_2") (pintype "passive"))
      (node (ref "C50") (pin "2") (pinfunction "2_2") (pintype "passive"))
      (node (ref "C51") (pin "2") (pinfunction "2_2") (pintype "passive"))
      (node (ref "C52") (pin "2") (pinfunction "2_2") (pintype "passive"))
      (node (ref "C53") (pin "2") (pinfunction "2_2") (pintype "passive"))
      (node (ref "C54") (pin "2") (pinfunction "2_2") (pintype "passive"))
      (node (ref "C55") (pin "2") (pinfunction "2_2") (pintype "passive"))
      (node (ref "C56") (pin "2") (pinfunction "2_2") (pintype "passive"))
      (node (ref "C57") (pin "2") (pinfunction "2_2") (pintype "passive"))
      (node (ref "C58") (pin "2") (pinfunction "2_2") (pintype "passive"))
      (node (ref "C59") (pin "2") (pinfunction "2_2") (pintype "passive"))
      (node (ref "C6") (pin "2") (pinfunction "2_2") (pintype "passive"))
      (node (ref "C60") (pin "2") (pinfunction "2_2") (pintype "passive"))
      (node (ref "C61") (pin "2") (pinfunction "2_2") (pintype "passive"))
      (node (ref "C62") (pin "2") (pinfunction "2_2") (pintype "passive"))
      (node (ref "C63") (pin "2") (pinfunction "2_2") (pintype "passive"))
      (node (ref "C64") (pin "2") (pinfunction "2_2") (pintype "passive"))
      (node (ref "C65") (pin "2") (pinfunction "2_2") (pintype "passive"))
      (node (ref "C66") (pin "2") (pinfunction "2_2") (pintype "passive"))
      (node (ref "C67") (pin "2") (pinfunction "2_2") (pintype "passive"))
      (node (ref "C68") (pin "2") (pinfunction "2_2") (pintype "passive"))
      (node (ref "C69") (pin "2") (pinfunction "2_2") (pintype "passive"))
      (node (ref "C7") (pin "2") (pinfunction "2_2") (pintype "passive"))
      (node (ref "C70") (pin "2") (pinfunction "2_2") (pintype "passive"))
      (node (ref "C71") (pin "2") (pinfunction "2_2") (pintype "passive"))
      (node (ref "C72") (pin "2") (pinfunction "2_2") (pintype "passive"))
      (node (ref "C73") (pin "2") (pinfunction "2_2") (pintype "passive"))
      (node (ref "C74") (pin "2") (pinfunction "2_2") (pintype "passive"))
      (node (ref "C75") (pin "2") (pinfunction "2_2") (pintype "passive"))
      (node (ref "C76") (pin "2") (pinfunction "2_2") (pintype "passive"))
      (node (ref "C77") (pin "2") (pinfunction "2_2") (pintype "passive"))
      (node (ref "C78") (pin "2") (pinfunction "2_2") (pintype "passive"))
      (node (ref "C79") (pin "2") (pinfunction "2_2") (pintype "passive"))
      (node (ref "C8") (pin "2") (pinfunction "2_2") (pintype "passive"))
      (node (ref "C80") (pin "2") (pinfunction "2_2") (pintype "passive"))
      (node (ref "C81") (pin "2") (pinfunction "2_2") (pintype "passive"))
      (node (ref "C82") (pin "2") (pinfunction "2_2") (pintype "passive"))
      (node (ref "C83") (pin "2") (pinfunction "2_2") (pintype "passive"))
      (node (ref "C84") (pin "2") (pinfunction "2_2") (pintype "passive"))
      (node (ref "C85") (pin "2") (pinfunction "2_2") (pintype "passive"))
      (node (ref "C86") (pin "2") (pinfunction "2_2") (pintype "passive"))
      (node (ref "C87") (pin "2") (pinfunction "2_2") (pintype "passive"))
      (node (ref "C88") (pin "2") (pinfunction "2_2") (pintype "passive"))
      (node (ref "C89") (pin "2") (pinfunction "2_2") (pintype "passive"))
      (node (ref "C9") (pin "2") (pinfunction "2_2") (pintype "passive"))
      (node (ref "C90") (pin "2") (pinfunction "2_2") (pintype "passive"))
      (node (ref "C91") (pin "2") (pinfunction "2_2") (pintype "passive"))
      (node (ref "C92") (pin "2") (pinfunction "2_2") (pintype "passive"))
      (node (ref "C93") (pin "2") (pinfunction "2_2") (pintype "passive"))
      (node (ref "C94") (pin "2") (pinfunction "2_2") (pintype "passive"))
      (node (ref "C95") (pin "2") (pinfunction "2_2") (pintype "passive"))
      (node (ref "C96") (pin "2") (pinfunction "2_2") (pintype "passive"))
      (node (ref "C97") (pin "2") (pinfunction "2_2") (pintype "passive"))
      (node (ref "C98") (pin "2") (pinfunction "2_2") (pintype "passive"))
      (node (ref "C99") (pin "2") (pinfunction "2_2") (pintype "passive"))
      (node (ref "D1") (pin "2") (pinfunction "VSS_2") (pintype "power_in"))
      (node (ref "D10") (pin "2") (pinfunction "VSS_2") (pintype "power_in"))
      (node (ref "D100") (pin "2") (pinfunction "VSS_2") (pintype "power_in"))
      (node (ref "D11") (pin "2") (pinfunction "VSS_2") (pintype "power_in"))
      (node (ref "D12") (pin "2") (pinfunction "VSS_2") (pintype "power_in"))
      (node (ref "D13") (pin "2") (pinfunction "VSS_2") (pintype "power_in"))
      (node (ref "D14") (pin "2") (pinfunction "VSS_2") (pintype "power_in"))
      (node (ref "D15") (pin "2") (pinfunction "VSS_2") (pintype "power_in"))
      (node (ref "D16") (pin "2") (pinfunction "VSS_2") (pintype "power_in"))
      (node (ref "D17") (pin "2") (pinfunction "VSS_2") (pintype "power_in"))
      (node (ref "D18") (pin "2") (pinfunction "VSS_2") (pintype "power_in"))
      (node (ref "D19") (pin "2") (pinfunction "VSS_2") (pintype "power_in"))
      (node (ref "D2") (pin "2") (pinfunction "VSS_2") (pintype "power_in"))
      (node (ref "D20") (pin "2") (pinfunction "VSS_2") (pintype "power_in"))
      (node (ref "D21") (pin "2") (pinfunction "VSS_2") (pintype "power_in"))
      (node (ref "D22") (pin "2") (pinfunction "VSS_2") (pintype "power_in"))
      (node (ref "D23") (pin "2") (pinfunction "VSS_2") (pintype "power_in"))
      (node (ref "D24") (pin "2") (pinfunction "VSS_2") (pintype "power_in"))
      (node (ref "D25") (pin "2") (pinfunction "VSS_2") (pintype "power_in"))
      (node (ref "D26") (pin "2") (pinfunction "VSS_2") (pintype "power_in"))
      (node (ref "D27") (pin "2") (pinfunction "VSS_2") (pintype "power_in"))
      (node (ref "D28") (pin "2") (pinfunction "VSS_2") (pintype "power_in"))
      (node (ref "D29") (pin "2") (pinfunction "VSS_2") (pintype "power_in"))
      (node (ref "D3") (pin "2") (pinfunction "VSS_2") (pintype "power_in"))
      (node (ref "D30") (pin "2") (pinfunction "VSS_2") (pintype "power_in"))
      (node (ref "D31") (pin "2") (pinfunction "VSS_2") (pintype "power_in"))
      (node (ref "D32") (pin "2") (pinfunction "VSS_2") (pintype "power_in"))
      (node (ref "D33") (pin "2") (pinfunction "VSS_2") (pintype "power_in"))
      (node (ref "D34") (pin "2") (pinfunction "VSS_2") (pintype "power_in"))
      (node (ref "D35") (pin "2") (pinfunction "VSS_2") (pintype "power_in"))
      (node (ref "D36") (pin "2") (pinfunction "VSS_2") (pintype "power_in"))
      (node (ref "D37") (pin "2") (pinfunction "VSS_2") (pintype "power_in"))
      (node (ref "D38") (pin "2") (pinfunction "VSS_2") (pintype "power_in"))
      (node (ref "D39") (pin "2") (pinfunction "VSS_2") (pintype "power_in"))
      (node (ref "D4") (pin "2") (pinfunction "VSS_2") (pintype "power_in"))
      (node (ref "D40") (pin "2") (pinfunction "VSS_2") (pintype "power_in"))
      (node (ref "D41") (pin "2") (pinfunction "VSS_2") (pintype "power_in"))
      (node (ref "D42") (pin "2") (pinfunction "VSS_2") (pintype "power_in"))
      (node (ref "D43") (pin "2") (pinfunction "VSS_2") (pintype "power_in"))
      (node (ref "D44") (pin "2") (pinfunction "VSS_2") (pintype "power_in"))
      (node (ref "D45") (pin "2") (pinfunction "VSS_2") (pintype "power_in"))
      (node (ref "D46") (pin "2") (pinfunction "VSS_2") (pintype "power_in"))
      (node (ref "D47") (pin "2") (pinfunction "VSS_2") (pintype "power_in"))
      (node (ref "D48") (pin "2") (pinfunction "VSS_2") (pintype "power_in"))
      (node (ref "D49") (pin "2") (pinfunction "VSS_2") (pintype "power_in"))
      (node (ref "D5") (pin "2") (pinfunction "VSS_2") (pintype "power_in"))
      (node (ref "D50") (pin "2") (pinfunction "VSS_2") (pintype "power_in"))
      (node (ref "D51") (pin "2") (pinfunction "VSS_2") (pintype "power_in"))
      (node (ref "D52") (pin "2") (pinfunction "VSS_2") (pintype "power_in"))
      (node (ref "D53") (pin "2") (pinfunction "VSS_2") (pintype "power_in"))
      (node (ref "D54") (pin "2") (pinfunction "VSS_2") (pintype "power_in"))
      (node (ref "D55") (pin "2") (pinfunction "VSS_2") (pintype "power_in"))
      (node (ref "D56") (pin "2") (pinfunction "VSS_2") (pintype "power_in"))
      (node (ref "D57") (pin "2") (pinfunction "VSS_2") (pintype "power_in"))
      (node (ref "D58") (pin "2") (pinfunction "VSS_2") (pintype "power_in"))
      (node (ref "D59") (pin "2") (pinfunction "VSS_2") (pintype "power_in"))
      (node (ref "D6") (pin "2") (pinfunction "VSS_2") (pintype "power_in"))
      (node (ref "D60") (pin "2") (pinfunction "VSS_2") (pintype "power_in"))
      (node (ref "D61") (pin "2") (pinfunction "VSS_2") (pintype "power_in"))
      (node (ref "D62") (pin "2") (pinfunction "VSS_2") (pintype "power_in"))
      (node (ref "D63") (pin "2") (pinfunction "VSS_2") (pintype "power_in"))
      (node (ref "D64") (pin "2") (pinfunction "VSS_2") (pintype "power_in"))
      (node (ref "D65") (pin "2") (pinfunction "VSS_2") (pintype "power_in"))
      (node (ref "D66") (pin "2") (pinfunction "VSS_2") (pintype "power_in"))
      (node (ref "D67") (pin "2") (pinfunction "VSS_2") (pintype "power_in"))
      (node (ref "D68") (pin "2") (pinfunction "VSS_2") (pintype "power_in"))
      (node (ref "D69") (pin "2") (pinfunction "VSS_2") (pintype "power_in"))
      (node (ref "D7") (pin "2") (pinfunction "VSS_2") (pintype "power_in"))
      (node (ref "D70") (pin "2") (pinfunction "VSS_2") (pintype "power_in"))
      (node (ref "D71") (pin "2") (pinfunction "VSS_2") (pintype "power_in"))
      (node (ref "D72") (pin "2") (pinfunction "VSS_2") (pintype "power_in"))
      (node (ref "D73") (pin "2") (pinfunction "VSS_2") (pintype "power_in"))
      (node (ref "D74") (pin "2") (pinfunction "VSS_2") (pintype "power_in"))
      (node (ref "D75") (pin "2") (pinfunction "VSS_2") (pintype "power_in"))
      (node (ref "D76") (pin "2") (pinfunction "VSS_2") (pintype "power_in"))
      (node (ref "D77") (pin "2") (pinfunction "VSS_2") (pintype "power_in"))
      (node (ref "D78") (pin "2") (pinfunction "VSS_2") (pintype "power_in"))
      (node (ref "D79") (pin "2") (pinfunction "VSS_2") (pintype "power_in"))
      (node (ref "D8") (pin "2") (pinfunction "VSS_2") (pintype "power_in"))
      (node (ref "D80") (pin "2") (pinfunction "VSS_2") (pintype "power_in"))
      (node (ref "D81") (pin "2") (pinfunction "VSS_2") (pintype "power_in"))
      (node (ref "D82") (pin "2") (pinfunction "VSS_2") (pintype "power_in"))
      (node (ref "D83") (pin "2") (pinfunction "VSS_2") (pintype "power_in"))
      (node (ref "D84") (pin "2") (pinfunction "VSS_2") (pintype "power_in"))
      (node (ref "D85") (pin "2") (pinfunction "VSS_2") (pintype "power_in"))
      (node (ref "D86") (pin "2") (pinfunction "VSS_2") (pintype "power_in"))
      (node (ref "D87") (pin "2") (pinfunction "VSS_2") (pintype "power_in"))
      (node (ref "D88") (pin "2") (pinfunction "VSS_2") (pintype "power_in"))
      (node (ref "D89") (pin "2") (pinfunction "VSS_2") (pintype "power_in"))
      (node (ref "D9") (pin "2") (pinfunction "VSS_2") (pintype "power_in"))
      (node (ref "D90") (pin "2") (pinfunction "VSS_2") (pintype "power_in"))
      (node (ref "D91") (pin "2") (pinfunction "VSS_2") (pintype "power_in"))
      (node (ref "D92") (pin "2") (pinfunction "VSS_2") (pintype "power_in"))
      (node (ref "D93") (pin "2") (pinfunction "VSS_2") (pintype "power_in"))
      (node (ref "D94") (pin "2") (pinfunction "VSS_2") (pintype "power_in"))
      (node (ref "D95") (pin "2") (pinfunction "VSS_2") (pintype "power_in"))
      (node (ref "D96") (pin "2") (pinfunction "VSS_2") (pintype "power_in"))
      (node (ref "D97") (pin "2") (pinfunction "VSS_2") (pintype "power_in"))
      (node (ref "D98") (pin "2") (pinfunction "VSS_2") (pintype "power_in"))
      (node (ref "D99") (pin "2") (pinfunction "VSS_2") (pintype "power_in"))
      (node (ref "J1") (pin "1") (pinfunction "1_1") (pintype "passive"))
    )
    (net (code "3") (name "Net-(D1-DIN)") (class "Default")
      (node (ref "D1") (pin "3") (pinfunction "DIN_3") (pintype "input"))
      (node (ref "J1") (pin "2") (pinfunction "2_2") (pintype "passive"))
    )
    (net (code "4") (name "Net-(D1-DOUT)") (class "Default")
      (node (ref "D1") (pin "1") (pinfunction "DOUT_1") (pintype "output"))
      (node (ref "D2") (pin "3") (pinfunction "DIN_3") (pintype "input"))
    )
    (net (code "5") (name "Net-(D2-DOUT)") (class "Default")
      (node (ref "D2") (pin "1") (pinfunction "DOUT_1") (pintype "output"))
      (node (ref "D3") (pin "3") (pinfunction "DIN_3") (pintype "input"))
    )
    (net (code "6") (name "Net-(D3-DOUT)") (class "Default")
      (node (ref "D3") (pin "1") (pinfunction "DOUT_1") (pintype "output"))
      (node (ref "D4") (pin "3") (pinfunction "DIN_3") (pintype "input"))
    )
    (net (code "7") (name "Net-(D4-DOUT)") (class "Default")
      (node (ref "D4") (pin "1") (pinfunction "DOUT_1") (pintype "output"))
      (node (ref "D5") (pin "3") (pinfunction "DIN_3") (pintype "input"))
    )
    (net (code "8") (name "Net-(D5-DOUT)") (class "Default")
      (node (ref "D5") (pin "1") (pinfunction "DOUT_1") (pintype "output"))
      (node (ref "D6") (pin "3") (pinfunction "DIN_3") (pintype "input"))
    )
    (net (code "9") (name "Net-(D6-DOUT)") (class "Default")
      (node (ref "D6") (pin "1") (pinfunction "DOUT_1") (pintype "output"))
      (node (ref "D7") (pin "3") (pinfunction "DIN_3") (pintype "input"))
    )
    (net (code "10") (name "Net-(D7-DOUT)") (class "Default")
      (node (ref "D7") (pin "1") (pinfunction "DOUT_1") (pintype "output"))
      (node (ref "D8") (pin "3") (pinfunction "DIN_3") (pintype "input"))
    )
    (net (code "11") (name "Net-(D8-DOUT)") (class "Default")
      (node (ref "D8") (pin "1") (pinfunction "DOUT_1") (pintype "output"))
      (node (ref "D9") (pin "3") (pinfunction "DIN_3") (pintype "input"))
    )
    (net (code "12") (name "Net-(D10-DIN)") (class "Default")
      (node (ref "D10") (pin "3") (pinfunction "DIN_3") (pintype "input"))
      (node (ref "D9") (pin "1") (pinfunction "DOUT_1") (pintype "output"))
    )
    (net (code "13") (name "Net-(D10-DOUT)") (class "Default")
      (node (ref "D10") (pin "1") (pinfunction "DOUT_1") (pintype "output"))
      (node (ref "D11") (pin "3") (pinfunction "DIN_3") (pintype "input"))
    )
    (net (code "14") (name "Net-(D11-DOUT)") (class "Default")
      (node (ref "D11") (pin "1") (pinfunction "DOUT_1") (pintype "output"))
      (node (ref "D12") (pin "3") (pinfunction "DIN_3") (pintype "input"))
    )
    (net (code "15") (name "Net-(D12-DOUT)") (class "Default")
      (node (ref "D12") (pin "1") (pinfunction "DOUT_1") (pintype "output"))
      (node (ref "D13") (pin "3") (pinfunction "DIN_3") (pintype "input"))
    )
    (net (code "16") (name "Net-(D13-DOUT)") (class "Default")
      (node (ref "D13") (pin "1") (pinfunction "DOUT_1") (pintype "output"))
      (node (ref "D14") (pin "3") (pinfunction "DIN_3") (pintype "input"))
    )
    (net (code "17") (name "Net-(D14-DOUT)") (class "Default")
      (node (ref "D14") (pin "1") (pinfunction "DOUT_1") (pintype "output"))
      (node (ref "D15") (pin "3") (pinfunction "DIN_3") (pintype "input"))
    )
    (net (code "18") (name "Net-(D15-DOUT)") (class "Default")
      (node (ref "D15") (pin "1") (pinfunction "DOUT_1") (pintype "output"))
      (node (ref "D16") (pin "3") (pinfunction "DIN_3") (pintype "input"))
    )
    (net (code "19") (name "Net-(D16-DOUT)") (class "Default")
      (node (ref "D16") (pin "1") (pinfunction "DOUT_1") (pintype "output"))
      (node (ref "D17") (pin "3") (pinfunction "DIN_3") (pintype "input"))
    )
    (net (code "20") (name "Net-(D17-DOUT)") (class "Default")
      (node (ref "D17") (pin "1") (pinfunction "DOUT_1") (pintype "output"))
      (node (ref "D18") (pin "3") (pinfunction "DIN_3") (pintype "input"))
    )
    (net (code "21") (name "Net-(D18-DOUT)") (class "Default")
      (node (ref "D18") (pin "1") (pinfunction "DOUT_1") (pintype "output"))
      (node (ref "D19") (pin "3") (pinfunction "DIN_3") (pintype "input"))
    )
    (net (code "22") (name "Net-(D19-DOUT)") (class "Default")
      (node (ref "D19") (pin "1") (pinfunction "DOUT_1") (pintype "output"))
      (node (ref "D20") (pin "3") (pinfunction "DIN_3") (pintype "input"))
    )
    (net (code "23") (name "Net-(D20-DOUT)") (class "Default")
      (node (ref "D20") (pin "1") (pinfunction "DOUT_1") (pintype "output"))
      (node (ref "D21") (pin "3") (pinfunction "DIN_3") (pintype "input"))
    )
    (net (code "24") (name "Net-(D21-DOUT)") (class "Default")
      (node (ref "D21") (pin "1") (pinfunction "DOUT_1") (pintype "output"))
      (node (ref "D22") (pin "3") (pinfunction "DIN_3") (pintype "input"))
    )
    (net (code "25") (name "Net-(D22-DOUT)") (class "Default")
      (node (ref "D22") (pin "1") (pinfunction "DOUT_1") (pintype "output"))
      (node (ref "D23") (pin "3") (pinfunction "DIN_3") (pintype "input"))
    )
    (net (code "26") (name "Net-(D23-DOUT)") (class "Default")
      (node (ref "D23") (pin "1") (pinfunction "DOUT_1") (pintype "output"))
      (node (ref "D24") (pin "3") (pinfunction "DIN_3") (pintype "input"))
    )
    (net (code "27") (name "Net-(D24-DOUT)") (class "Default")
      (node (ref "D24") (pin "1") (pinfunction "DOUT_1") (pintype "output"))
      (node (ref "D25") (pin "3") (pinfunction "DIN_3") (pintype "input"))
    )
    (net (code "28") (name "Net-(D25-DOUT)") (class "Default")
      (node (ref "D25") (pin "1") (pinfunction "DOUT_1") (pintype "output"))
      (node (ref "D26") (pin "3") (pinfunction "DIN_3") (pintype "input"))
    )
    (net (code "29") (name "Net-(D26-DOUT)") (class "Default")
      (node (ref "D26") (pin "1") (pinfunction "DOUT_1") (pintype "output"))
      (node (ref "D27") (pin "3") (pinfunction "DIN_3") (pintype "input"))
    )
    (net (code "30") (name "Net-(D27-DOUT)") (class "Default")
      (node (ref "D27") (pin "1") (pinfunction "DOUT_1") (pintype "output"))
      (node (ref "D28") (pin "3") (pinfunction "DIN_3") (pintype "input"))
    )
    (net (code "31") (name "Net-(D28-DOUT)") (class "Default")
      (node (ref "D28") (pin "1") (pinfunction "DOUT_1") (pintype "output"))
      (node (ref "D29") (pin "3") (pinfunction "DIN_3") (pintype "input"))
    )
    (net (code "32") (name "Net-(D29-DOUT)") (class "Default")
      (node (ref "D29") (pin "1") (pinfunction "DOUT_1") (pintype "output"))
      (node (ref "D30") (pin "3") (pinfunction "DIN_3") (pintype "input"))
    )
    (net (code "33") (name "Net-(D30-DOUT)") (class "Default")
      (node (ref "D30") (pin "1") (pinfunction "DOUT_1") (pintype "output"))
      (node (ref "D31") (pin "3") (pinfunction "DIN_3") (pintype "input"))
    )
    (net (code "34") (name "Net-(D31-DOUT)") (class "Default")
      (node (ref "D31") (pin "1") (pinfunction "DOUT_1") (pintype "output"))
      (node (ref "D32") (pin "3") (pinfunction "DIN_3") (pintype "input"))
    )
    (net (code "35") (name "Net-(D32-DOUT)") (class "Default")
      (node (ref "D32") (pin "1") (pinfunction "DOUT_1") (pintype "output"))
      (node (ref "D33") (pin "3") (pinfunction "DIN_3") (pintype "input"))
    )
    (net (code "36") (name "Net-(D33-DOUT)") (class "Default")
      (node (ref "D33") (pin "1") (pinfunction "DOUT_1") (pintype "output"))
      (node (ref "D34") (pin "3") (pinfunction "DIN_3") (pintype "input"))
    )
    (net (code "37") (name "Net-(D34-DOUT)") (class "Default")
      (node (ref "D34") (pin "1") (pinfunction "DOUT_1") (pintype "output"))
      (node (ref "D35") (pin "3") (pinfunction "DIN_3") (pintype "input"))
    )
    (net (code "38") (name "Net-(D35-DOUT)") (class "Default")
      (node (ref "D35") (pin "1") (pinfunction "DOUT_1") (pintype "output"))
      (node (ref "D36") (pin "3") (pinfunction "DIN_3") (pintype "input"))
    )
    (net (code "39") (name "Net-(D36-DOUT)") (class "Default")
      (node (ref "D36") (pin "1") (pinfunction "DOUT_1") (pintype "output"))
      (node (ref "D37") (pin "3") (pinfunction "DIN_3") (pintype "input"))
    )
    (net (code "40") (name "Net-(D37-DOUT)") (class "Default")
      (node (ref "D37") (pin "1") (pinfunction "DOUT_1") (pintype "output"))
      (node (ref "D38") (pin "3") (pinfunction "DIN_3") (pintype "input"))
    )
    (net (code "41") (name "Net-(D38-DOUT)") (class "Default")
      (node (ref "D38") (pin "1") (pinfunction "DOUT_1") (pintype "output"))
      (node (ref "D39") (pin "3") (pinfunction "DIN_3") (pintype "input"))
    )
    (net (code "42") (name "Net-(D39-DOUT)") (class "Default")
      (node (ref "D39") (pin "1") (pinfunction "DOUT_1") (pintype "output"))
      (node (ref "D40") (pin "3") (pinfunction "DIN_3") (pintype "input"))
    )
    (net (code "43") (name "Net-(D40-DOUT)") (class "Default")
      (node (ref "D40") (pin "1") (pinfunction "DOUT_1") (pintype "output"))
      (node (ref "D41") (pin "3") (pinfunction "DIN_3") (pintype "input"))
    )
    (net (code "44") (name "Net-(D41-DOUT)") (class "Default")
      (node (ref "D41") (pin "1") (pinfunction "DOUT_1") (pintype "output"))
      (node (ref "D42") (pin "3") (pinfunction "DIN_3") (pintype "input"))
    )
    (net (code "45") (name "Net-(D42-DOUT)") (class "Default")
      (node (ref "D42") (pin "1") (pinfunction "DOUT_1") (pintype "output"))
      (node (ref "D43") (pin "3") (pinfunction "DIN_3") (pintype "input"))
    )
    (net (code "46") (name "Net-(D43-DOUT)") (class "Default")
      (node (ref "D43") (pin "1") (pinfunction "DOUT_1") (pintype "output"))
      (node (ref "D44") (pin "3") (pinfunction "DIN_3") (pintype "input"))
    )
    (net (code "47") (name "Net-(D44-DOUT)") (class "Default")
      (node (ref "D44") (pin "1") (pinfunction "DOUT_1") (pintype "output"))
      (node (ref "D45") (pin "3") (pinfunction "DIN_3") (pintype "input"))
    )
    (net (code "48") (name "Net-(D45-DOUT)") (class "Default")
      (node (ref "D45") (pin "1") (pinfunction "DOUT_1") (pintype "output"))
      (node (ref "D46") (pin "3") (pinfunction "DIN_3") (pintype "input"))
    )
    (net (code "49") (name "Net-(D46-DOUT)") (class "Default")
      (node (ref "D46") (pin "1") (pinfunction "DOUT_1") (pintype "output"))
      (node (ref "D47") (pin "3") (pinfunction "DIN_3") (pintype "input"))
    )
    (net (code "50") (name "Net-(D47-DOUT)") (class "Default")
      (node (ref "D47") (pin "1") (pinfunction "DOUT_1") (pintype "output"))
      (node (ref "D48") (pin "3") (pinfunction "DIN_3") (pintype "input"))
    )
    (net (code "51") (name "Net-(D48-DOUT)") (class "Default")
      (node (ref "D48") (pin "1") (pinfunction "DOUT_1") (pintype "output"))
      (node (ref "D49") (pin "3") (pinfunction "DIN_3") (pintype "input"))
    )
    (net (code "52") (name "Net-(D49-DOUT)") (class "Default")
      (node (ref "D49") (pin "1") (pinfunction "DOUT_1") (pintype "output"))
      (node (ref "D50") (pin "3") (pinfunction "DIN_3") (pintype "input"))
    )
    (net (code "53") (name "Net-(D50-DOUT)") (class "Default")
      (node (ref "D50") (pin "1") (pinfunction "DOUT_1") (pintype "output"))
      (node (ref "D51") (pin "3") (pinfunction "DIN_3") (pintype "input"))
    )
    (net (code "54") (name "Net-(D51-DOUT)") (class "Default")
      (node (ref "D51") (pin "1") (pinfunction "DOUT_1") (pintype "output"))
      (node (ref "D52") (pin "3") (pinfunction "DIN_3") (pintype "input"))
    )
    (net (code "55") (name "Net-(D52-DOUT)") (class "Default")
      (node (ref "D52") (pin "1") (pinfunction "DOUT_1") (pintype "output"))
      (node (ref "D53") (pin "3") (pinfunction "DIN_3") (pintype "input"))
    )
    (net (code "56") (name "Net-(D53-DOUT)") (class "Default")
      (node (ref "D53") (pin "1") (pinfunction "DOUT_1") (pintype "output"))
      (node (ref "D54") (pin "3") (pinfunction "DIN_3") (pintype "input"))
    )
    (net (code "57") (name "Net-(D54-DOUT)") (class "Default")
      (node (ref "D54") (pin "1") (pinfunction "DOUT_1") (pintype "output"))
      (node (ref "D55") (pin "3") (pinfunction "DIN_3") (pintype "input"))
    )
    (net (code "58") (name "Net-(D55-DOUT)") (class "Default")
      (node (ref "D55") (pin "1") (pinfunction "DOUT_1") (pintype "output"))
      (node (ref "D56") (pin "3") (pinfunction "DIN_3") (pintype "input"))
    )
    (net (code "59") (name "Net-(D56-DOUT)") (class "Default")
      (node (ref "D56") (pin "1") (pinfunction "DOUT_1") (pintype "output"))
      (node (ref "D57") (pin "3") (pinfunction "DIN_3") (pintype "input"))
    )
    (net (code "60") (name "Net-(D57-DOUT)") (class "Default")
      (node (ref "D57") (pin "1") (pinfunction "DOUT_1") (pintype "output"))
      (node (ref "D58") (pin "3") (pinfunction "DIN_3") (pintype "input"))
    )
    (net (code "61") (name "Net-(D58-DOUT)") (class "Default")
      (node (ref "D58") (pin "1") (pinfunction "DOUT_1") (pintype "output"))
      (node (ref "D59") (pin "3") (pinfunction "DIN_3") (pintype "input"))
    )
    (net (code "62") (name "Net-(D59-DOUT)") (class "Default")
      (node (ref "D59") (pin "1") (pinfunction "DOUT_1") (pintype "output"))
      (node (ref "D60") (pin "3") (pinfunction "DIN_3") (pintype "input"))
    )
    (net (code "63") (name "Net-(D60-DOUT)") (class "Default")
      (node (ref "D60") (pin "1") (pinfunction "DOUT_1") (pintype "output"))
      (node (ref "D61") (pin "3") (pinfunction "DIN_3") (pintype "input"))
    )
    (net (code "64") (name "Net-(D61-DOUT)") (class "Default")
      (node (ref "D61") (pin "1") (pinfunction "DOUT_1") (pintype "output"))
      (node (ref "D62") (pin "3") (pinfunction "DIN_3") (pintype "input"))
    )
    (net (code "65") (name "Net-(D62-DOUT)") (class "Default")
      (node (ref "D62") (pin "1") (pinfunction "DOUT_1") (pintype "output"))
      (node (ref "D63") (pin "3") (pinfunction "DIN_3") (pintype "input"))
    )
    (net (code "66") (name "Net-(D63-DOUT)") (class "Default")
      (node (ref "D63") (pin "1") (pinfunction "DOUT_1") (pintype "output"))
      (node (ref "D64") (pin "3") (pinfunction "DIN_3") (pintype "input"))
    )
    (net (code "67") (name "Net-(D64-DOUT)") (class "Default")
      (node (ref "D64") (pin "1") (pinfunction "DOUT_1") (pintype "output"))
      (node (ref "D65") (pin "3") (pinfunction "DIN_3") (pintype "input"))
    )
    (net (code "68") (name "Net-(D65-DOUT)") (class "Default")
      (node (ref "D65") (pin "1") (pinfunction "DOUT_1") (pintype "output"))
      (node (ref "D66") (pin "3") (pinfunction "DIN_3") (pintype "input"))
    )
    (net (code "69") (name "Net-(D66-DOUT)") (class "Default")
      (node (ref "D66") (pin "1") (pinfunction "DOUT_1") (pintype "output"))
      (node (ref "D67") (pin "3") (pinfunction "DIN_3") (pintype "input"))
    )
    (net (code "70") (name "Net-(D67-DOUT)") (class "Default")
      (node (ref "D67") (pin "1") (pinfunction "DOUT_1") (pintype "output"))
      (node (ref "D68") (pin "3") (pinfunction "DIN_3") (pintype "input"))
    )
    (net (code "71") (name "Net-(D68-DOUT)") (class "Default")
      (node (ref "D68") (pin "1") (pinfunction "DOUT_1") (pintype "output"))
      (node (ref "D69") (pin "3") (pinfunction "DIN_3") (pintype "input"))
    )
    (net (code "72") (name "Net-(D69-DOUT)") (class "Default")
      (node (ref "D69") (pin "1") (pinfunction "DOUT_1") (pintype "output"))
      (node (ref "D70") (pin "3") (pinfunction "DIN_3") (pintype "input"))
    )
    (net (code "73") (name "Net-(D70-DOUT)") (class "Default")
      (node (ref "D70") (pin "1") (pinfunction "DOUT_1") (pintype "output"))
      (node (ref "D71") (pin "3") (pinfunction "DIN_3") (pintype "input"))
    )
    (net (code "74") (name "Net-(D71-DOUT)") (class "Default")
      (node (ref "D71") (pin "1") (pinfunction "DOUT_1") (pintype "output"))
      (node (ref "D72") (pin "3") (pinfunction "DIN_3") (pintype "input"))
    )
    (net (code "75") (name "Net-(D72-DOUT)") (class "Default")
      (node (ref "D72") (pin "1") (pinfunction "DOUT_1") (pintype "output"))
      (node (ref "D73") (pin "3") (pinfunction "DIN_3") (pintype "input"))
    )
    (net (code "76") (name "Net-(D73-DOUT)") (class "Default")
      (node (ref "D73") (pin "1") (pinfunction "DOUT_1") (pintype "output"))
      (node (ref "D74") (pin "3") (pinfunction "DIN_3") (pintype "input"))
    )
    (net (code "77") (name "Net-(D74-DOUT)") (class "Default")
      (node (ref "D74") (pin "1") (pinfunction "DOUT_1") (pintype "output"))
      (node (ref "D75") (pin "3") (pinfunction "DIN_3") (pintype "input"))
    )
    (net (code "78") (name "Net-(D75-DOUT)") (class "Default")
      (node (ref "D75") (pin "1") (pinfunction "DOUT_1") (pintype "output"))
      (node (ref "D76") (pin "3") (pinfunction "DIN_3") (pintype "input"))
    )
    (net (code "79") (name "Net-(D76-DOUT)") (class "Default")
      (node (ref "D76") (pin "1") (pinfunction "DOUT_1") (pintype "output"))
      (node (ref "D77") (pin "3") (pinfunction "DIN_3") (pintype "input"))
    )
    (net (code "80") (name "Net-(D77-DOUT)") (class "Default")
      (node (ref "D77") (pin "1") (pinfunction "DOUT_1") (pintype "output"))
      (node (ref "D78") (pin "3") (pinfunction "DIN_3") (pintype "input"))
    )
    (net (code "81") (name "Net-(D78-DOUT)") (class "Default")
      (node (ref "D78") (pin "1") (pinfunction "DOUT_1") (pintype "output"))
      (node (ref "D79") (pin "3") (pinfunction "DIN_3") (pintype "input"))
    )
    (net (code "82") (name "Net-(D79-DOUT)") (class "Default")
      (node (ref "D79") (pin "1") (pinfunction "DOUT_1") (pintype "output"))
      (node (ref "D80") (pin "3") (pinfunction "DIN_3") (pintype "input"))
    )
    (net (code "83") (name "Net-(D80-DOUT)") (class "Default")
      (node (ref "D80") (pin "1") (pinfunction "DOUT_1") (pintype "output"))
      (node (ref "D81") (pin "3") (pinfunction "DIN_3") (pintype "input"))
    )
    (net (code "84") (name "Net-(D81-DOUT)") (class "Default")
      (node (ref "D81") (pin "1") (pinfunction "DOUT_1") (pintype "output"))
      (node (ref "D82") (pin "3") (pinfunction "DIN_3") (pintype "input"))
    )
    (net (code "85") (name "Net-(D82-DOUT)") (class "Default")
      (node (ref "D82") (pin "1") (pinfunction "DOUT_1") (pintype "output"))
      (node (ref "D83") (pin "3") (pinfunction "DIN_3") (pintype "input"))
    )
    (net (code "86") (name "Net-(D83-DOUT)") (class "Default")
      (node (ref "D83") (pin "1") (pinfunction "DOUT_1") (pintype "output"))
      (node (ref "D84") (pin "3") (pinfunction "DIN_3") (pintype "input"))
    )
    (net (code "87") (name "Net-(D84-DOUT)") (class "Default")
      (node (ref "D84") (pin "1") (pinfunction "DOUT_1") (pintype "output"))
      (node (ref "D85") (pin "3") (pinfunction "DIN_3") (pintype "input"))
    )
    (net (code "88") (name "Net-(D85-DOUT)") (class "Default")
      (node (ref "D85") (pin "1") (pinfunction "DOUT_1") (pintype "output"))
      (node (ref "D86") (pin "3") (pinfunction "DIN_3") (pintype "input"))
    )
    (net (code "89") (name "Net-(D86-DOUT)") (class "Default")
      (node (ref "D86") (pin "1") (pinfunction "DOUT_1") (pintype "output"))
      (node (ref "D87") (pin "3") (pinfunction "DIN_3") (pintype "input"))
    )
    (net (code "90") (name "Net-(D87-DOUT)") (class "Default")
      (node (ref "D87") (pin "1") (pinfunction "DOUT_1") (pintype "output"))
      (node (ref "D88") (pin "3") (pinfunction "DIN_3") (pintype "input"))
    )
    (net (code "91") (name "Net-(D88-DOUT)") (class "Default")
      (node (ref "D88") (pin "1") (pinfunction "DOUT_1") (pintype "output"))
      (node (ref "D89") (pin "3") (pinfunction "DIN_3") (pintype "input"))
    )
    (net (code "92") (name "Net-(D89-DOUT)") (class "Default")
      (node (ref "D89") (pin "1") (pinfunction "DOUT_1") (pintype "output"))
      (node (ref "D90") (pin "3") (pinfunction "DIN_3") (pintype "input"))
    )
    (net (code "93") (name "Net-(D90-DOUT)") (class "Default")
      (node (ref "D90") (pin "1") (pinfunction "DOUT_1") (pintype "output"))
      (node (ref "D91") (pin "3") (pinfunction "DIN_3") (pintype "input"))
    )
    (net (code "94") (name "Net-(D91-DOUT)") (class "Default")
      (node (ref "D91") (pin "1") (pinfunction "DOUT_1") (pintype "output"))
      (node (ref "D92") (pin "3") (pinfunction "DIN_3") (pintype "input"))
    )
    (net (code "95") (name "Net-(D92-DOUT)") (class "Default")
      (node (ref "D92") (pin "1") (pinfunction "DOUT_1") (pintype "output"))
      (node (ref "D93") (pin "3") (pinfunction "DIN_3") (pintype "input"))
    )
    (net (code "96") (name "Net-(D93-DOUT)") (class "Default")
      (node (ref "D93") (pin "1") (pinfunction "DOUT_1") (pintype "output"))
      (node (ref "D94") (pin "3") (pinfunction "DIN_3") (pintype "input"))
    )
    (net (code "97") (name "Net-(D94-DOUT)") (class "Default")
      (node (ref "D94") (pin "1") (pinfunction "DOUT_1") (pintype "output"))
      (node (ref "D95") (pin "3") (pinfunction "DIN_3") (pintype "input"))
    )
    (net (code "98") (name "Net-(D95-DOUT)") (class "Default")
      (node (ref "D95") (pin "1") (pinfunction "DOUT_1") (pintype "output"))
      (node (ref "D96") (pin "3") (pinfunction "DIN_3") (pintype "input"))
    )
    (net (code "99") (name "Net-(D96-DOUT)") (class "Default")
      (node (ref "D96") (pin "1") (pinfunction "DOUT_1") (pintype "output"))
      (node (ref "D97") (pin "3") (pinfunction "DIN_3") (pintype "input"))
    )
    (net (code "100") (name "Net-(D97-DOUT)") (class "Default")
      (node (ref "D97") (pin "1") (pinfunction "DOUT_1") (pintype "output"))
      (node (ref "D98") (pin "3") (pinfunction "DIN_3") (pintype "input"))
    )
    (net (code "101") (name "Net-(D98-DOUT)") (class "Default")
      (node (ref "D98") (pin "1") (pinfunction "DOUT_1") (pintype "output"))
      (node (ref "D99") (pin "3") (pinfunction "DIN_3") (pintype "input"))
    )
    (net (code "102") (name "Net-(D100-DIN)") (class "Default")
      (node (ref "D100") (pin "3") (pinfunction "DIN_3") (pintype "input"))
      (node (ref "D99") (pin "1") (pinfunction "DOUT_1") (pintype "output"))
    )
    (net (code "103") (name "unconnected-(D100-DOUT-Pad1)") (class "Default")
      (node (ref "D100") (pin "1") (pinfunction "DOUT_1") (pintype "output"))
    )
    (net (code "104") (name "unconnected-(J1-Pad3)") (class "Default")
      (node (ref "J1") (pin "3") (pinfunction "3_3") (pintype "passive"))
    )
    (net (code "105") (name "unconnected-(J1-Pad5)") (class "Default")
      (node (ref "J1") (pin "5") (pinfunction "5_5") (pintype "passive"))
    )
    (net (code "106") (name "unconnected-(J1-Pad6)") (class "Default")
      (node (ref "J1") (pin "6") (pinfunction "6_6") (pintype "passive"))
    )
  )
)
